# 0831.net
KiCad netlist of a schematic drawn in Altium Designer
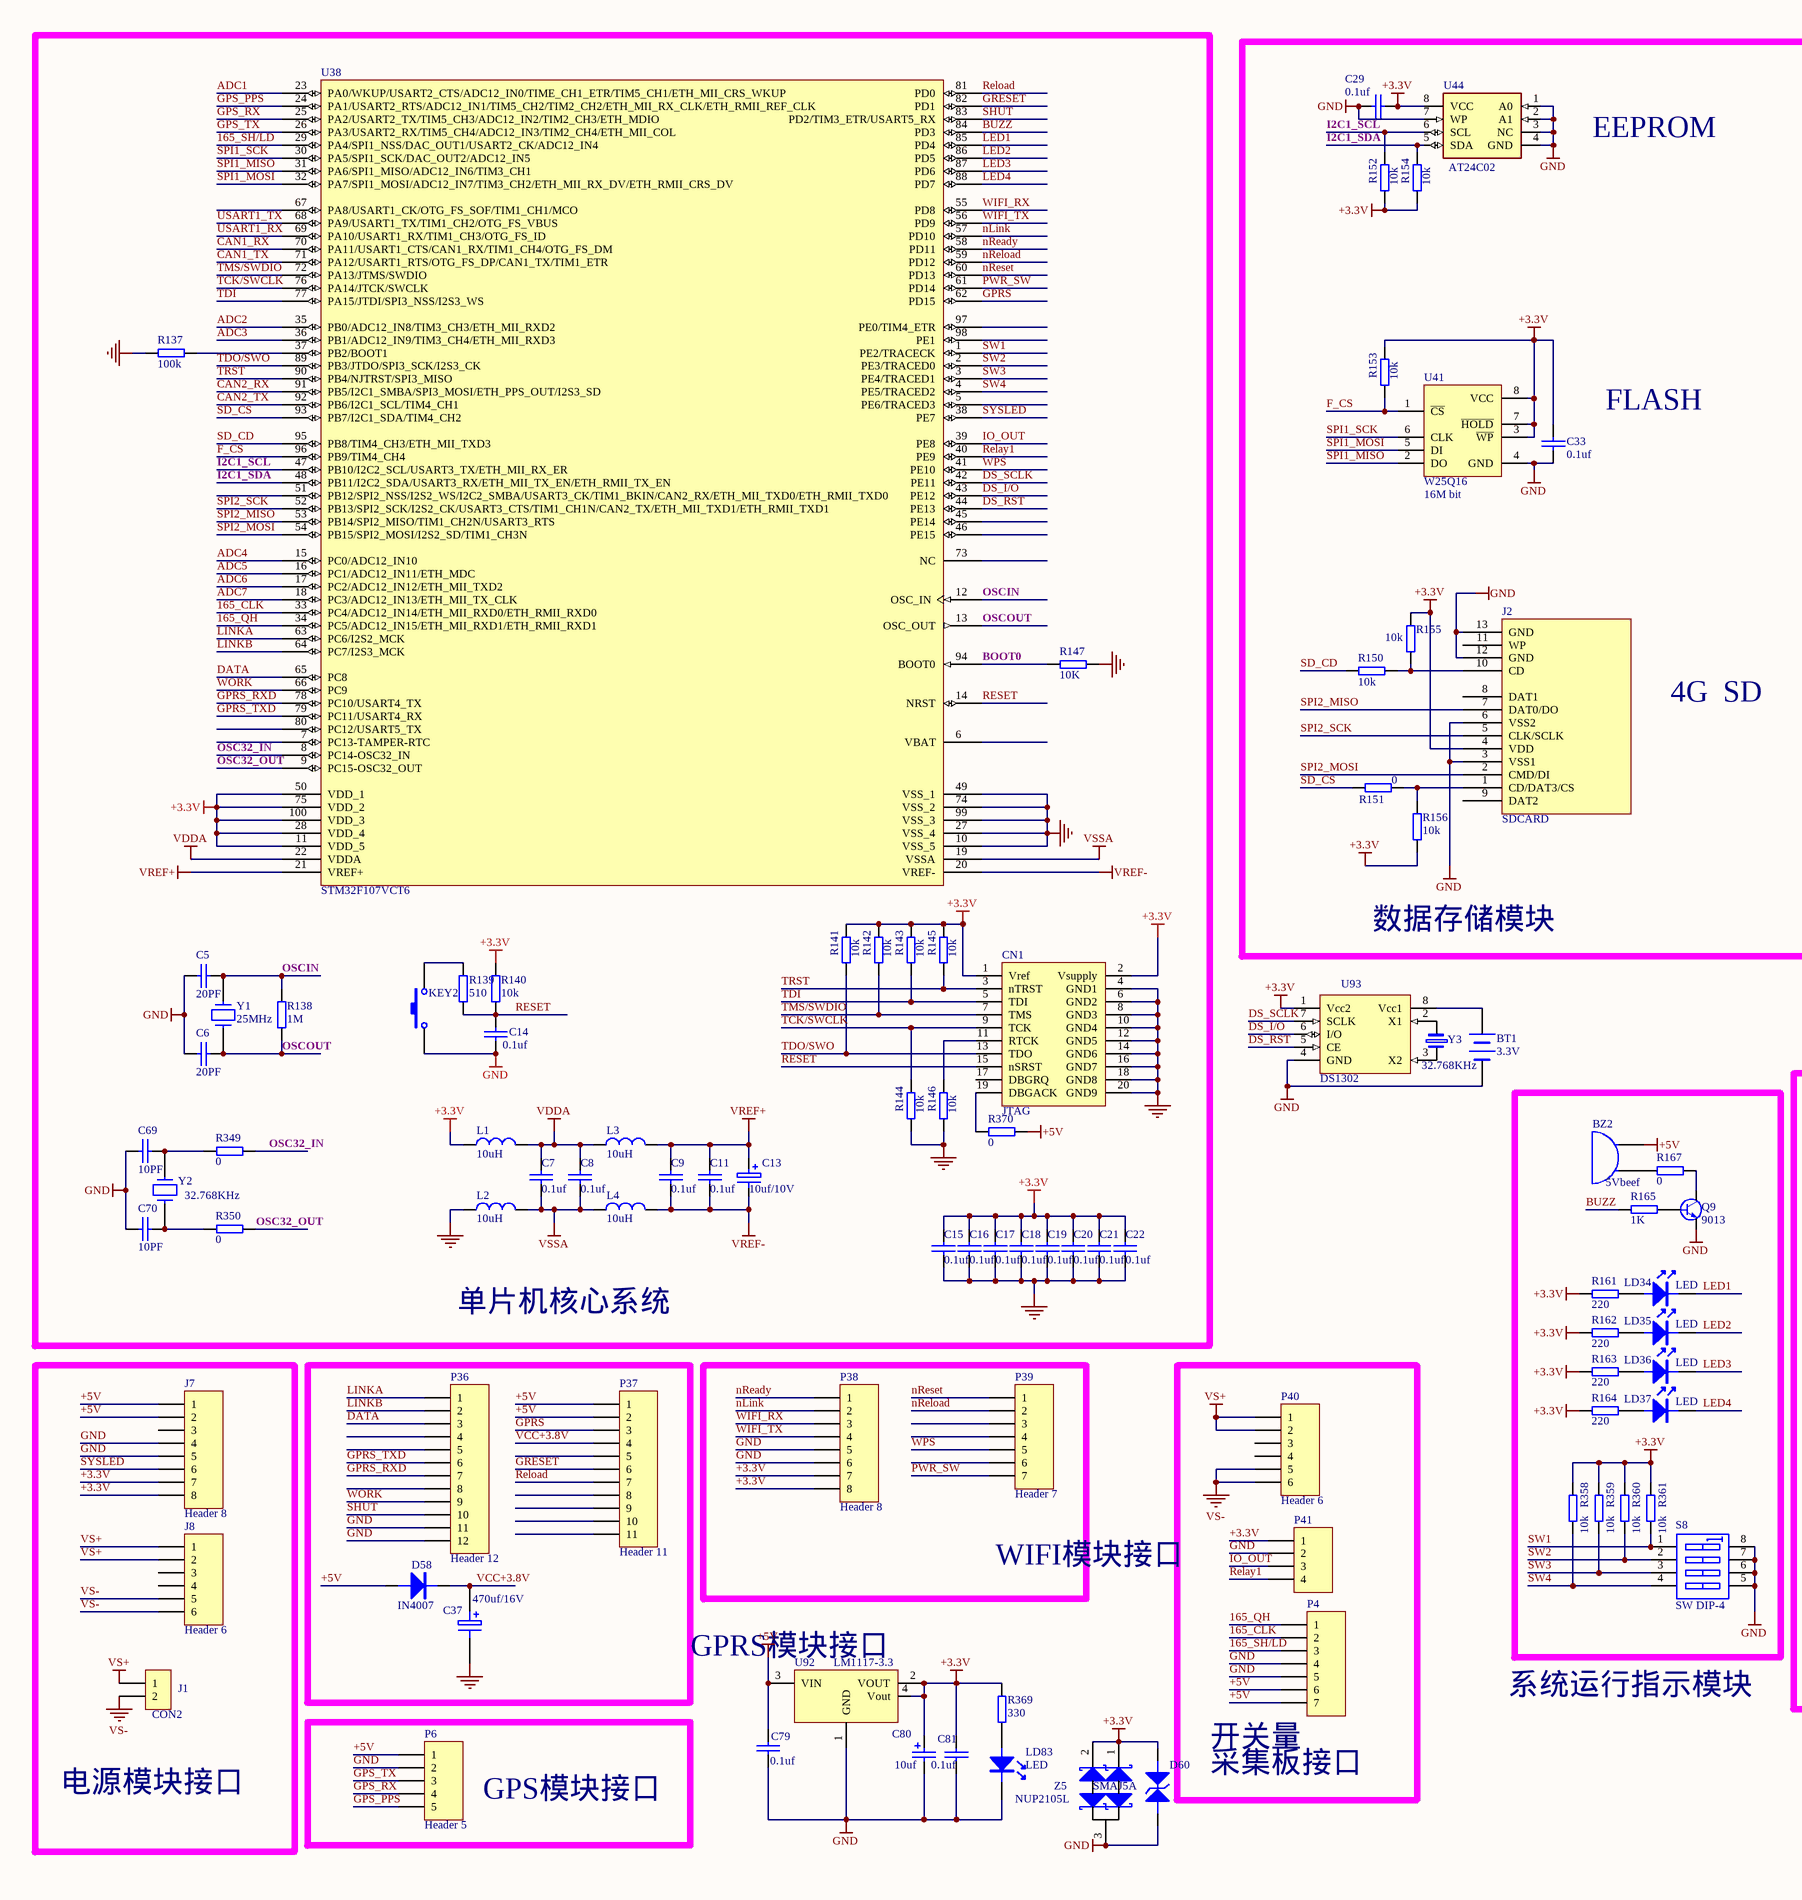
[diagram p0: 如意硬件系统模块0831.SchDoc, left]
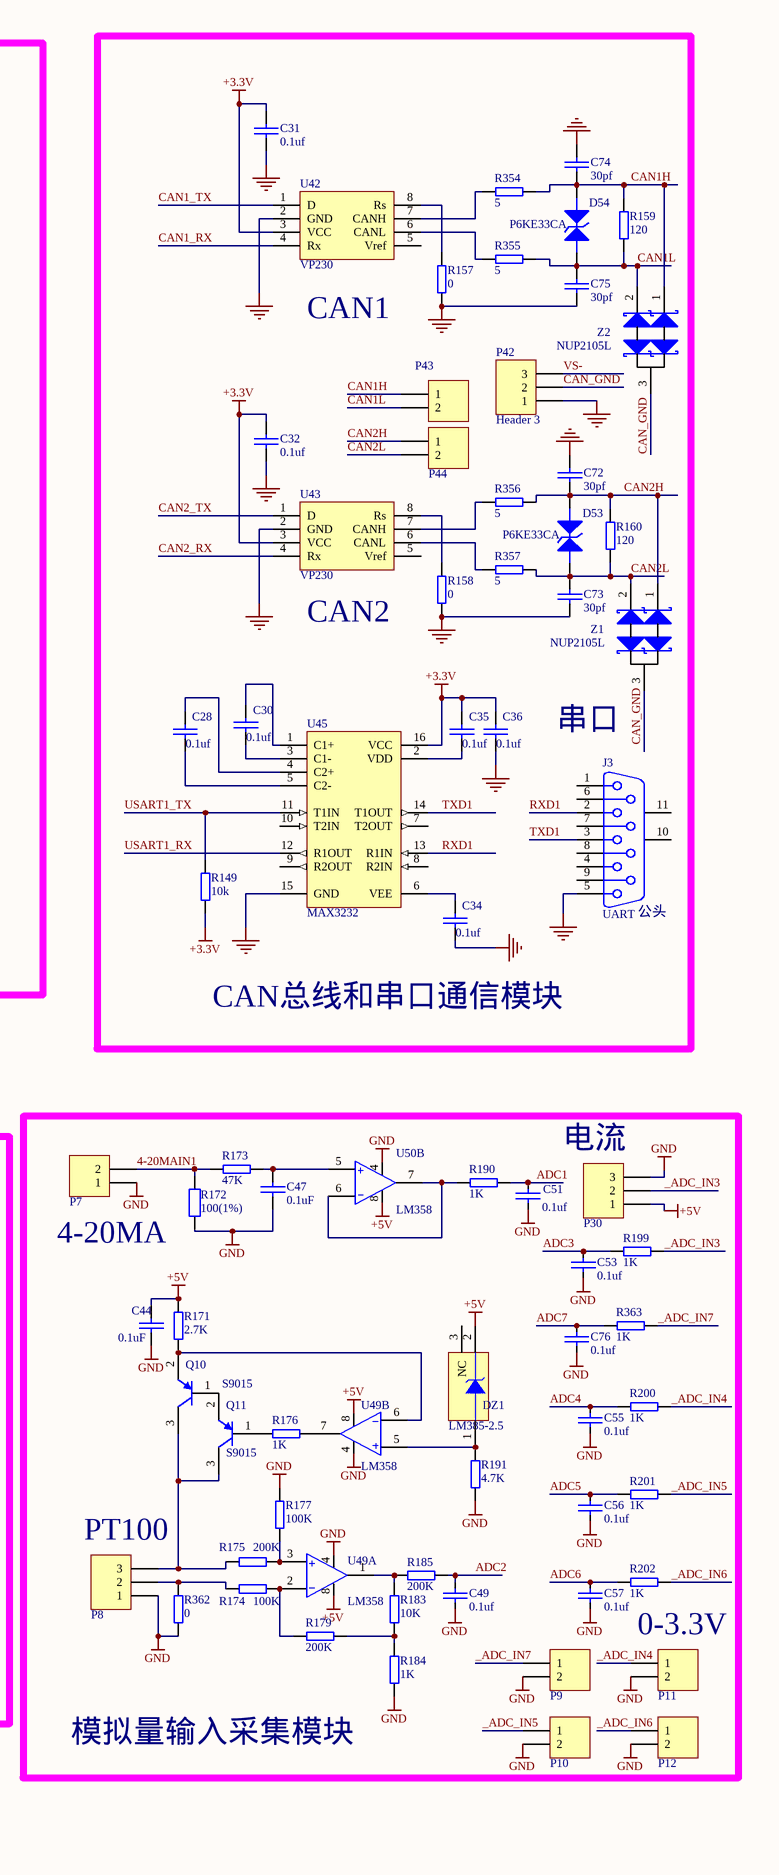
[diagram p1: 如意硬件系统模块0831.SchDoc, right]

(export (version "E")
  (design (tool "Eeschema 10.0.6"))
  (components
    (comp (ref "BT1")
      (value "3.3V")
      (footprint "BT2")
      (description "Battery")
      (libsource (lib "*") (part "BATTERY"))
    )
    (comp (ref "BZ2") (value "5Vbeef") (footprint "BEEP") (libsource (lib "*") (part "BUZZER")))
    (comp (ref "C5")
      (value "20PF")
      (footprint "0603C-1")
      (description "Capacitor")
      (libsource (lib "") (part "CAP_1"))
    )
    (comp (ref "C6")
      (value "20PF")
      (footprint "0603C-1")
      (description "Capacitor")
      (libsource (lib "") (part "CAP_1"))
    )
    (comp (ref "C7")
      (value "0.1uf")
      (footprint "0603C-1")
      (description "Capacitor")
      (libsource (lib "*") (part "CAP"))
    )
    (comp (ref "C8")
      (value "0.1uf")
      (footprint "0603C-1")
      (description "Capacitor")
      (libsource (lib "*") (part "CAP"))
    )
    (comp (ref "C9")
      (value "0.1uf")
      (footprint "0603C-1")
      (description "Capacitor")
      (libsource (lib "*") (part "CAP"))
    )
    (comp (ref "C11")
      (value "0.1uf")
      (footprint "0603C-1")
      (description "Capacitor")
      (libsource (lib "*") (part "CAP"))
    )
    (comp (ref "C13") (value "10uf/10V") (footprint "1206D-S") (libsource (lib "*") (part "JXC")))
    (comp (ref "C14")
      (value "0.1uf")
      (footprint "0603C-1")
      (description "Capacitor")
      (libsource (lib "") (part "CAP_1"))
    )
    (comp (ref "C15")
      (value "0.1uf")
      (footprint "0603C-1")
      (description "Capacitor")
      (libsource (lib "*") (part "CAP"))
    )
    (comp (ref "C16")
      (value "0.1uf")
      (footprint "0603C-1")
      (description "Capacitor")
      (libsource (lib "*") (part "CAP"))
    )
    (comp (ref "C17")
      (value "0.1uf")
      (footprint "0603C-1")
      (description "Capacitor")
      (libsource (lib "*") (part "CAP"))
    )
    (comp (ref "C18")
      (value "0.1uf")
      (footprint "0603C-1")
      (description "Capacitor")
      (libsource (lib "*") (part "CAP"))
    )
    (comp (ref "C19")
      (value "0.1uf")
      (footprint "0603C-1")
      (description "Capacitor")
      (libsource (lib "*") (part "CAP"))
    )
    (comp (ref "C20")
      (value "0.1uf")
      (footprint "0603C-1")
      (description "Capacitor")
      (libsource (lib "*") (part "CAP"))
    )
    (comp (ref "C21")
      (value "0.1uf")
      (footprint "0603C-1")
      (description "Capacitor")
      (libsource (lib "*") (part "CAP"))
    )
    (comp (ref "C22")
      (value "0.1uf")
      (footprint "0603C-1")
      (description "Capacitor")
      (libsource (lib "*") (part "CAP"))
    )
    (comp (ref "C28")
      (value "0.1uf")
      (footprint "0603C-1")
      (description "Capacitor")
      (libsource (lib "") (part "CAP_1"))
    )
    (comp (ref "C29")
      (value "0.1uf")
      (footprint "0603C-1")
      (description "Capacitor")
      (libsource (lib "") (part "CAP_1"))
    )
    (comp (ref "C30")
      (value "0.1uf")
      (footprint "0603C-1")
      (description "Capacitor")
      (libsource (lib "") (part "CAP_1"))
    )
    (comp (ref "C31")
      (value "0.1uf")
      (footprint "0603C-1")
      (description "Capacitor")
      (libsource (lib "") (part "CAP_1"))
    )
    (comp (ref "C32")
      (value "0.1uf")
      (footprint "0603C-1")
      (description "Capacitor")
      (libsource (lib "") (part "CAP_1"))
    )
    (comp (ref "C33")
      (value "0.1uf")
      (footprint "0603C-1")
      (description "Capacitor")
      (libsource (lib "") (part "CAP_1"))
    )
    (comp (ref "C34")
      (value "0.1uf")
      (footprint "0603C-1")
      (description "Capacitor")
      (libsource (lib "") (part "CAP_1"))
    )
    (comp (ref "C35")
      (value "0.1uf")
      (footprint "0603C-1")
      (description "Capacitor")
      (libsource (lib "") (part "CAP_1"))
    )
    (comp (ref "C36")
      (value "0.1uf")
      (footprint "0603C-1")
      (description "Capacitor")
      (libsource (lib "") (part "CAP_1"))
    )
    (comp (ref "C37")
      (value "470uf/16V")
      (footprint "C-RB-10")
      (description "Electrolytic Capacitor")
      (libsource (lib "*") (part "ELECTRO1"))
    )
    (comp (ref "C44")
      (value "0.1uF")
      (footprint "0603C-1")
      (description "Capacitor")
      (libsource (lib "") (part "CAP_1"))
    )
    (comp (ref "C47")
      (value "0.1uF")
      (footprint "0603C-1")
      (description "Capacitor")
      (libsource (lib "") (part "CAP_1"))
    )
    (comp (ref "C49") (value "0.1uf") (footprint "0805-1") (libsource (lib "*") (part "C")))
    (comp (ref "C51") (value "0.1uf") (footprint "0603C-1") (libsource (lib "*") (part "C")))
    (comp (ref "C53") (value "0.1uf") (footprint "0603C-1") (libsource (lib "*") (part "C")))
    (comp (ref "C55") (value "0.1uf") (footprint "0603C-1") (libsource (lib "*") (part "C")))
    (comp (ref "C56") (value "0.1uf") (footprint "0603C-1") (libsource (lib "*") (part "C")))
    (comp (ref "C57") (value "0.1uf") (footprint "0603C-1") (libsource (lib "*") (part "C")))
    (comp (ref "C69")
      (value "10PF")
      (footprint "0603C-1")
      (description "Capacitor")
      (libsource (lib "") (part "CAP_1"))
    )
    (comp (ref "C70")
      (value "10PF")
      (footprint "0603C-1")
      (description "Capacitor")
      (libsource (lib "") (part "CAP_1"))
    )
    (comp (ref "C72")
      (value "30pf")
      (footprint "0805-1")
      (description "Capacitor")
      (libsource (lib "") (part "CAP_1"))
    )
    (comp (ref "C73")
      (value "30pf")
      (footprint "0805-1")
      (description "Capacitor")
      (libsource (lib "") (part "CAP_1"))
    )
    (comp (ref "C74")
      (value "30pf")
      (footprint "0805-1")
      (description "Capacitor")
      (libsource (lib "") (part "CAP_1"))
    )
    (comp (ref "C75")
      (value "30pf")
      (footprint "0805-1")
      (description "Capacitor")
      (libsource (lib "") (part "CAP_1"))
    )
    (comp (ref "C76") (value "0.1uf") (footprint "0603C-1") (libsource (lib "*") (part "C")))
    (comp (ref "C79")
      (value "0.1uf")
      (footprint "0603C-1")
      (description "CAP")
      (libsource (lib "*") (part "CAP0"))
    )
    (comp (ref "C80") (value "10uf") (footprint "1206D-S") (libsource (lib "*") (part "ECAP")))
    (comp (ref "C81")
      (value "0.1uf")
      (footprint "0603C-1")
      (description "CAP")
      (libsource (lib "*") (part "CAP0"))
    )
    (comp (ref "CN1") (value "JTAG") (footprint "JTAG20 - 15") (libsource (lib "zongruyi") (part "JTAG20")))
    (comp (ref "D53") (value "P6KE33CA") (footprint "SMB") (libsource (lib "*") (part "TVS")))
    (comp (ref "D54") (value "P6KE33CA") (footprint "SMB") (libsource (lib "*") (part "TVS")))
    (comp (ref "D58")
      (value "IN4007")
      (footprint "SMB")
      (description "Diode")
      (libsource (lib "*") (part "DIODE"))
    )
    (comp (ref "D60") (value "SMAJ5A") (footprint "SMB") (libsource (lib "*") (part "TVS")))
    (comp (ref "DZ1")
      (value "LM385-2.5")
      (footprint "TO-92A")
      (description "Micropower Voltage Reference Diode")
      (fields (field (name "PUBLISHER") "Altium Limited"))
      (libsource (lib "*") (part "LM385BYZ-2.5"))
    )
    (comp (ref "J1")
      (value "CON2")
      (footprint "JXZ-2")
      (description "Connector")
      (libsource (lib "*") (part "CON2"))
    )
    (comp (ref "J2")
      (value "SDCARD")
      (footprint "SDC009-01-R2")
      (description "SD卡自弹")
      (libsource (lib "Fszhang") (part "SDCARD"))
    )
    (comp (ref "J3")
      (value "UART")
      (footprint "DB9-M")
      (description "Receptacle Assembly, 9 Position, Right Angle")
      (fields (field (name "PUBLISHER") "Altium Limited"))
      (libsource (lib "zongruyi") (part "D Connector 9"))
    )
    (comp (ref "J7")
      (value "Header 8")
      (footprint "HDR1X8")
      (description "Header, 8-Pin")
      (fields (field (name "PUBLISHER") "Altium Limited"))
      (libsource (lib "Miscellaneous Connectors") (part "Header 8"))
    )
    (comp (ref "J8")
      (value "Header 6")
      (footprint "HDR1X6")
      (description "接插件")
      (fields (field (name "PUBLISHER") "Altium Limited"))
      (libsource (lib "Miscellaneous Connectors") (part "Header 6"))
    )
    (comp (ref "KEY2")
      (value "SW-PB")
      (footprint "SW_PB4_A1")
      (description "Switch")
      (fields (field (name "PUBLISHER") "Altium Limited"))
      (libsource (lib "*") (part "SW-PB"))
    )
    (comp (ref "L1")
      (value "10uH")
      (footprint "1206")
      (description "电感")
      (fields (field (name "Comment") "Inductor") (field (name "PUBLISHER") "Altium Limited"))
      (libsource (lib "Fszhang") (part "Inductor"))
    )
    (comp (ref "L2")
      (value "10uH")
      (footprint "1206")
      (description "电感")
      (fields (field (name "Comment") "Inductor") (field (name "PUBLISHER") "Altium Limited"))
      (libsource (lib "Fszhang") (part "Inductor"))
    )
    (comp (ref "L3")
      (value "10uH")
      (footprint "1206")
      (description "电感")
      (fields (field (name "Comment") "Inductor") (field (name "PUBLISHER") "Altium Limited"))
      (libsource (lib "Fszhang") (part "Inductor"))
    )
    (comp (ref "L4")
      (value "10uH")
      (footprint "1206")
      (description "电感")
      (fields (field (name "Comment") "Inductor") (field (name "PUBLISHER") "Altium Limited"))
      (libsource (lib "Fszhang") (part "Inductor"))
    )
    (comp (ref "LD34") (value "LED") (footprint "LED_0805") (libsource (lib "*") (part "LED")))
    (comp (ref "LD35") (value "LED") (footprint "LED_0805") (libsource (lib "*") (part "LED")))
    (comp (ref "LD36") (value "LED") (footprint "LED_0805") (libsource (lib "*") (part "LED")))
    (comp (ref "LD37") (value "LED") (footprint "LED_0805") (libsource (lib "*") (part "LED")))
    (comp (ref "LD83") (value "LED") (footprint "LED_0805") (libsource (lib "") (part "LED_1")))
    (comp (ref "P4")
      (value "Header 7")
      (footprint "HDR1X7")
      (description "Header, 7-Pin")
      (fields (field (name "PUBLISHER") "Altium Limited"))
      (libsource (lib "Miscellaneous Connectors") (part "Header 7"))
    )
    (comp (ref "P6")
      (value "Header 5")
      (footprint "HDR1X5")
      (description "Header, 5-Pin")
      (fields (field (name "PUBLISHER") "Altium Limited"))
      (libsource (lib "Miscellaneous Connectors") (part "Header 5"))
    )
    (comp (ref "P7")
      (value "Header 2")
      (footprint "KF3.81-2P")
      (description "接插件")
      (fields (field (name "PUBLISHER") "Altium Limited"))
      (libsource (lib "") (part "Header 2_1"))
    )
    (comp (ref "P8")
      (value "Header 3")
      (footprint "KF3.81-3P")
      (description "接插件")
      (fields (field (name "PUBLISHER") "Altium Limited"))
      (libsource (lib "Fszhang") (part "Header 3"))
    )
    (comp (ref "P9")
      (value "Header 2")
      (footprint "KF3.81-2P")
      (description "接插件")
      (fields (field (name "PUBLISHER") "Altium Limited"))
      (libsource (lib "Fszhang") (part "Header 2"))
    )
    (comp (ref "P10")
      (value "Header 2")
      (footprint "KF3.81-2P")
      (description "接插件")
      (fields (field (name "PUBLISHER") "Altium Limited"))
      (libsource (lib "Fszhang") (part "Header 2"))
    )
    (comp (ref "P11")
      (value "Header 2")
      (footprint "KF3.81-2P")
      (description "接插件")
      (fields (field (name "PUBLISHER") "Altium Limited"))
      (libsource (lib "Fszhang") (part "Header 2"))
    )
    (comp (ref "P12")
      (value "Header 2")
      (footprint "KF3.81-2P")
      (description "接插件")
      (fields (field (name "PUBLISHER") "Altium Limited"))
      (libsource (lib "Fszhang") (part "Header 2"))
    )
    (comp (ref "P30")
      (value "Header 3")
      (footprint "KF3.81-3P")
      (description "接插件")
      (fields (field (name "PUBLISHER") "Altium Limited"))
      (libsource (lib "Fszhang") (part "Header 3"))
    )
    (comp (ref "P36")
      (value "Header 12")
      (footprint "HDR1X12")
      (description "Header, 12-Pin")
      (fields (field (name "PUBLISHER") "Altium Limited"))
      (libsource (lib "Miscellaneous Connectors") (part "Header 12"))
    )
    (comp (ref "P37")
      (value "Header 11")
      (footprint "HDR1X11")
      (description "Header, 11-Pin")
      (fields (field (name "PUBLISHER") "Altium Limited"))
      (libsource (lib "Miscellaneous Connectors") (part "Header 11"))
    )
    (comp (ref "P38")
      (value "Header 8")
      (footprint "HDR1X8")
      (description "Header, 8-Pin")
      (fields (field (name "PUBLISHER") "Altium Limited"))
      (libsource (lib "Miscellaneous Connectors") (part "Header 8"))
    )
    (comp (ref "P39")
      (value "Header 7")
      (footprint "HDR1X7")
      (description "Header, 7-Pin")
      (fields (field (name "PUBLISHER") "Altium Limited"))
      (libsource (lib "Miscellaneous Connectors") (part "Header 7"))
    )
    (comp (ref "P40")
      (value "Header 6")
      (footprint "HDR1X6")
      (description "Header, 6-Pin")
      (fields (field (name "PUBLISHER") "Altium Limited"))
      (libsource (lib "Miscellaneous Connectors") (part "Header 6"))
    )
    (comp (ref "P41")
      (value "Header 4")
      (footprint "HDR1X4")
      (description "Header, 4-Pin")
      (fields (field (name "PUBLISHER") "Altium Limited"))
      (libsource (lib "Miscellaneous Connectors") (part "Header 4"))
    )
    (comp (ref "P42")
      (value "Header 3")
      (footprint "HDR1X3")
      (description "Header, 3-Pin")
      (fields (field (name "PUBLISHER") "Altium Limited"))
      (libsource (lib "Miscellaneous Connectors") (part "Header 3"))
    )
    (comp (ref "P43")
      (value "Header 2")
      (footprint "KF3.81-2P")
      (description "接插件")
      (fields (field (name "PUBLISHER") "Altium Limited"))
      (libsource (lib "Fszhang") (part "Header 2"))
    )
    (comp (ref "P44")
      (value "Header 2")
      (footprint "KF3.81-2P")
      (description "接插件")
      (fields (field (name "PUBLISHER") "Altium Limited"))
      (libsource (lib "Fszhang") (part "Header 2"))
    )
    (comp (ref "Q9") (value "9013") (footprint "SOT23-BCE") (libsource (lib "*") (part "NPN")))
    (comp (ref "Q10")
      (value "S9015")
      (footprint "SOT-23")
      (description "PNP三极管")
      (fields (field (name "PUBLISHER") "Altium Limited"))
      (libsource (lib "zongruyi") (part "S9015_1"))
    )
    (comp (ref "Q11")
      (value "S9015")
      (footprint "SOT-23")
      (description "PNP三极管")
      (fields (field (name "PUBLISHER") "Altium Limited"))
      (libsource (lib "zongruyi") (part "S9015_1"))
    )
    (comp (ref "R137") (value "100k") (footprint "0603R-1") (libsource (lib "*") (part "RES2")))
    (comp (ref "R138") (value "1M") (footprint "0603R-1") (libsource (lib "*") (part "RES-2")))
    (comp (ref "R139") (value "510") (footprint "0603R-1") (libsource (lib "*") (part "RES-2")))
    (comp (ref "R140") (value "10k") (footprint "0603R-1") (libsource (lib "*") (part "RES2")))
    (comp (ref "R141") (value "10k") (footprint "0603R-1") (libsource (lib "*") (part "RES2")))
    (comp (ref "R142") (value "10k") (footprint "0603R-1") (libsource (lib "*") (part "RES2")))
    (comp (ref "R143") (value "10k") (footprint "0603R-1") (libsource (lib "*") (part "RES2")))
    (comp (ref "R144") (value "10k") (footprint "0603R-1") (libsource (lib "*") (part "RES2")))
    (comp (ref "R145") (value "10k") (footprint "0603R-1") (libsource (lib "*") (part "RES2")))
    (comp (ref "R146") (value "10k") (footprint "0603R-1") (libsource (lib "*") (part "RES2")))
    (comp (ref "R147") (value "10K") (footprint "0603R-1") (libsource (lib "*") (part "RES-2")))
    (comp (ref "R149") (value "10k") (footprint "0603R-1") (libsource (lib "*") (part "RES2")))
    (comp (ref "R150") (value "10k") (footprint "0603R-1") (libsource (lib "*") (part "RES2")))
    (comp (ref "R151") (value "0") (footprint "0603R-1") (libsource (lib "*") (part "RES2")))
    (comp (ref "R152") (value "10k") (footprint "0603R-1") (libsource (lib "*") (part "RES2")))
    (comp (ref "R153") (value "10k") (footprint "0603R-1") (libsource (lib "*") (part "RES2")))
    (comp (ref "R154") (value "10k") (footprint "0603R-1") (libsource (lib "*") (part "RES2")))
    (comp (ref "R155") (value "10k") (footprint "0603R-1") (libsource (lib "*") (part "RES2")))
    (comp (ref "R156") (value "10k") (footprint "0603R-1") (libsource (lib "*") (part "RES2")))
    (comp (ref "R157") (value "0") (footprint "0603R-1") (libsource (lib "*") (part "RES2")))
    (comp (ref "R158") (value "0") (footprint "0603R-1") (libsource (lib "*") (part "RES2")))
    (comp (ref "R159") (value "120") (footprint "0805-1") (libsource (lib "*") (part "RES2")))
    (comp (ref "R160") (value "120") (footprint "0805-1") (libsource (lib "*") (part "RES2")))
    (comp (ref "R161") (value "220") (footprint "0603R-1") (libsource (lib "") (part "RES-2_1")))
    (comp (ref "R162") (value "220") (footprint "0603R-1") (libsource (lib "") (part "RES-2_1")))
    (comp (ref "R163") (value "220") (footprint "0603R-1") (libsource (lib "") (part "RES-2_1")))
    (comp (ref "R164") (value "220") (footprint "0603R-1") (libsource (lib "") (part "RES-2_1")))
    (comp (ref "R165") (value "1K") (footprint "0603R-1") (libsource (lib "") (part "RES-2_1")))
    (comp (ref "R167") (value "0") (footprint "0603R-1") (libsource (lib "") (part "RES-2_1")))
    (comp (ref "R171") (value "2.7K") (footprint "AXIAL0.4") (libsource (lib "") (part "RES-2_1")))
    (comp (ref "R172")
      (value "100(1%)")
      (footprint "AXIAL0.4")
      (description "Resistor")
      (fields (field (name "PUBLISHER") "Altium Limited"))
      (libsource (lib "*") (part "Res2"))
    )
    (comp (ref "R173") (value "47K") (footprint "0603R-1") (libsource (lib "*") (part "RES-2")))
    (comp (ref "R174") (value "100K") (footprint "0805-1") (libsource (lib "") (part "RES-2_1")))
    (comp (ref "R175") (value "200K") (footprint "0805-1") (libsource (lib "") (part "RES-2_1")))
    (comp (ref "R176") (value "1K") (footprint "0603R-1") (libsource (lib "") (part "RES-2_1")))
    (comp (ref "R177") (value "100K") (footprint "0805-1") (libsource (lib "") (part "RES-2_1")))
    (comp (ref "R179") (value "200K") (footprint "0805-1") (libsource (lib "") (part "RES-2_1")))
    (comp (ref "R183") (value "10K") (footprint "0805-1") (libsource (lib "") (part "RES-2_1")))
    (comp (ref "R184") (value "1K") (footprint "0805-1") (libsource (lib "") (part "RES-2_1")))
    (comp (ref "R185") (value "200K") (footprint "0805-1") (libsource (lib "") (part "RES-2_1")))
    (comp (ref "R190") (value "1K") (footprint "0603R-1") (libsource (lib "*") (part "RES-2")))
    (comp (ref "R191") (value "4.7K") (footprint "0603R-1") (libsource (lib "") (part "RES-2_1")))
    (comp (ref "R199") (value "1K") (footprint "0603R-1") (libsource (lib "*") (part "RES-2")))
    (comp (ref "R200") (value "1K") (footprint "0603R-1") (libsource (lib "*") (part "RES-2")))
    (comp (ref "R201") (value "1K") (footprint "0603R-1") (libsource (lib "*") (part "RES-2")))
    (comp (ref "R202") (value "1K") (footprint "0603R-1") (libsource (lib "*") (part "RES-2")))
    (comp (ref "R349") (value "0") (footprint "0603R-1") (libsource (lib "*") (part "RES-2")))
    (comp (ref "R350") (value "0") (footprint "0603R-1") (libsource (lib "*") (part "RES-2")))
    (comp (ref "R354") (value "5") (footprint "0805-1") (libsource (lib "*") (part "RES2")))
    (comp (ref "R355") (value "5") (footprint "0805-1") (libsource (lib "*") (part "RES2")))
    (comp (ref "R356") (value "5") (footprint "0805-1") (libsource (lib "*") (part "RES2")))
    (comp (ref "R357") (value "5") (footprint "0805-1") (libsource (lib "*") (part "RES2")))
    (comp (ref "R358") (value "10k") (footprint "0603R-1") (libsource (lib "*") (part "RES2")))
    (comp (ref "R359") (value "10k") (footprint "0603R-1") (libsource (lib "*") (part "RES2")))
    (comp (ref "R360") (value "10k") (footprint "0603R-1") (libsource (lib "*") (part "RES2")))
    (comp (ref "R361") (value "10k") (footprint "0603R-1") (libsource (lib "*") (part "RES2")))
    (comp (ref "R362") (value "0") (footprint "0603R-1") (libsource (lib "*") (part "RES2")))
    (comp (ref "R363") (value "1K") (footprint "0603R-1") (libsource (lib "*") (part "RES-2")))
    (comp (ref "R369") (value "330") (footprint "0603R-1") (libsource (lib "*") (part "RES-2")))
    (comp (ref "R370") (value "0") (footprint "0603R-1") (libsource (lib "*") (part "RES2")))
    (comp (ref "S8")
      (value "SW DIP-4")
      (footprint "DIP-8")
      (description "编码开关")
      (fields (field (name "PUBLISHER") "Altium Limited"))
      (libsource (lib "Fszhang") (part "SW DIP-4"))
    )
    (comp (ref "U38")
      (value "STM32F107VCT6")
      (footprint "LQFP100_M")
      (libsource (lib "金龙107原理图封装库") (part "STM32F107VCT6"))
    )
    (comp (ref "U41")
      (value "W25Q16")
      (footprint "SOIC8_W")
      (description "SPI FLASH")
      (fields (field (name "MEMORY") "16M bit"))
      (libsource (lib "Fszhang") (part "W25QXX"))
    )
    (comp (ref "U42")
      (value "VP230")
      (footprint "NSO8_N")
      (description "CAN芯片")
      (libsource (lib "Fszhang") (part "SN65HVD230"))
    )
    (comp (ref "U43")
      (value "VP230")
      (footprint "NSO8_N")
      (description "CAN芯片")
      (libsource (lib "Fszhang") (part "SN65HVD230"))
    )
    (comp (ref "U44") (value "AT24C02") (footprint "SO-8") (libsource (lib "*") (part "AT24C128")))
    (comp (ref "U45")
      (value "MAX3232")
      (footprint "NSO16_M")
      (description "+5V Powered, Multi-Channel RS-232 Driver/Receiver")
      (fields (field (name "PUBLISHER") "Altium Limited"))
      (libsource (lib "Fszhang") (part "MAX232"))
    )
    (comp (ref "U49") (value "LM358") (footprint "SO-8") (libsource (lib "*") (part "LM358")))
    (comp (ref "U50") (value "LM358") (footprint "SO-8") (libsource (lib "*") (part "LM358")))
    (comp (ref "U92") (value "LM1117-3.3") (footprint "ASM1117") (libsource (lib "*") (part "LM1117")))
    (comp (ref "U93") (value "DS1302") (footprint "SO-8") (libsource (lib "*") (part "DS1302")))
    (comp (ref "Y1")
      (value "25MHz")
      (footprint "XTAL1")
      (description "Crystal")
      (libsource (lib "*") (part "CRYSTAL"))
    )
    (comp (ref "Y2")
      (value "32.768KHz")
      (footprint "XTAL4")
      (description "Crystal")
      (libsource (lib "*") (part "CRYSTAL"))
    )
    (comp (ref "Y3") (value "32.768KHz") (footprint "XTAL5") (libsource (lib "*") (part "XTAL")))
    (comp (ref "Z1")
      (value "NUP2105L")
      (footprint "SOT-23")
      (description "过压保护")
      (libsource (lib "Fszhang") (part "PESD1CAN"))
    )
    (comp (ref "Z2")
      (value "NUP2105L")
      (footprint "SOT-23")
      (description "过压保护")
      (libsource (lib "Fszhang") (part "PESD1CAN"))
    )
    (comp (ref "Z5")
      (value "NUP2105L")
      (footprint "SOT-23")
      (description "过压保护")
      (libsource (lib "Fszhang") (part "PESD1CAN"))
    )
  )
  (nets
    (net (code "1") (name "+3.3V") (class "Default")
      (node (ref "C15") (pin "2") (pinfunction "2_2") (pintype "passive"))
      (node (ref "C16") (pin "2") (pinfunction "2_2") (pintype "passive"))
      (node (ref "C17") (pin "2") (pinfunction "2_2") (pintype "passive"))
      (node (ref "C18") (pin "2") (pinfunction "2_2") (pintype "passive"))
      (node (ref "C19") (pin "2") (pinfunction "2_2") (pintype "passive"))
      (node (ref "C20") (pin "2") (pinfunction "2_2") (pintype "passive"))
      (node (ref "C21") (pin "2") (pinfunction "2_2") (pintype "passive"))
      (node (ref "C22") (pin "2") (pinfunction "2_2") (pintype "passive"))
      (node (ref "C29") (pin "2") (pinfunction "2_2") (pintype "passive"))
      (node (ref "C31") (pin "2") (pinfunction "2_2") (pintype "passive"))
      (node (ref "C32") (pin "2") (pinfunction "2_2") (pintype "passive"))
      (node (ref "C33") (pin "2") (pinfunction "2_2") (pintype "passive"))
      (node (ref "C35") (pin "2") (pinfunction "2_2") (pintype "passive"))
      (node (ref "C36") (pin "2") (pinfunction "2_2") (pintype "passive"))
      (node (ref "C80") (pin "1") (pintype "passive"))
      (node (ref "C81") (pin "2") (pintype "passive"))
      (node (ref "CN1") (pin "1") (pinfunction "Vref_1") (pintype "passive"))
      (node (ref "CN1") (pin "2") (pinfunction "Vsupply_2") (pintype "passive"))
      (node (ref "D60") (pin "2") (pinfunction "K_2") (pintype "passive"))
      (node (ref "J2") (pin "4") (pinfunction "VDD_4") (pintype "passive"))
      (node (ref "J7") (pin "7") (pinfunction "7_7") (pintype "passive"))
      (node (ref "J7") (pin "8") (pinfunction "8_8") (pintype "passive"))
      (node (ref "L1") (pin "1") (pinfunction "1_1") (pintype "passive"))
      (node (ref "P38") (pin "7") (pinfunction "7_7") (pintype "passive"))
      (node (ref "P38") (pin "8") (pinfunction "8_8") (pintype "passive"))
      (node (ref "P41") (pin "1") (pinfunction "1_1") (pintype "passive"))
      (node (ref "R140") (pin "2") (pinfunction "2_2") (pintype "passive"))
      (node (ref "R141") (pin "2") (pinfunction "2_2") (pintype "passive"))
      (node (ref "R142") (pin "2") (pinfunction "2_2") (pintype "passive"))
      (node (ref "R143") (pin "2") (pinfunction "2_2") (pintype "passive"))
      (node (ref "R145") (pin "2") (pinfunction "2_2") (pintype "passive"))
      (node (ref "R149") (pin "2") (pinfunction "2_2") (pintype "passive"))
      (node (ref "R152") (pin "1") (pinfunction "1_1") (pintype "passive"))
      (node (ref "R153") (pin "2") (pinfunction "2_2") (pintype "passive"))
      (node (ref "R154") (pin "1") (pinfunction "1_1") (pintype "passive"))
      (node (ref "R155") (pin "1") (pinfunction "1_1") (pintype "passive"))
      (node (ref "R156") (pin "2") (pinfunction "2_2") (pintype "passive"))
      (node (ref "R161") (pin "1") (pinfunction "1_1") (pintype "passive"))
      (node (ref "R162") (pin "1") (pinfunction "1_1") (pintype "passive"))
      (node (ref "R163") (pin "1") (pinfunction "1_1") (pintype "passive"))
      (node (ref "R164") (pin "1") (pinfunction "1_1") (pintype "passive"))
      (node (ref "R358") (pin "2") (pinfunction "2_2") (pintype "passive"))
      (node (ref "R359") (pin "2") (pinfunction "2_2") (pintype "passive"))
      (node (ref "R360") (pin "2") (pinfunction "2_2") (pintype "passive"))
      (node (ref "R361") (pin "2") (pinfunction "2_2") (pintype "passive"))
      (node (ref "R369") (pin "1") (pinfunction "1_1") (pintype "passive"))
      (node (ref "U38") (pin "100") (pinfunction "VDD_3_100") (pintype "passive"))
      (node (ref "U38") (pin "11") (pinfunction "VDD_5_11") (pintype "passive"))
      (node (ref "U38") (pin "28") (pinfunction "VDD_4_28") (pintype "passive"))
      (node (ref "U38") (pin "50") (pinfunction "VDD_1_50") (pintype "passive"))
      (node (ref "U38") (pin "75") (pinfunction "VDD_2_75") (pintype "passive"))
      (node (ref "U41") (pin "3") (pinfunction "~{WP}_3") (pintype "passive"))
      (node (ref "U41") (pin "7") (pinfunction "~{HOLD}_7") (pintype "passive"))
      (node (ref "U41") (pin "8") (pinfunction "VCC_8") (pintype "passive"))
      (node (ref "U42") (pin "3") (pinfunction "VCC_3") (pintype "passive"))
      (node (ref "U43") (pin "3") (pinfunction "VCC_3") (pintype "passive"))
      (node (ref "U44") (pin "8") (pinfunction "VCC_8") (pintype "power_in"))
      (node (ref "U45") (pin "16") (pinfunction "VCC_16") (pintype "power_in"))
      (node (ref "U92") (pin "2") (pinfunction "VOUT_2") (pintype "passive"))
      (node (ref "U92") (pin "4") (pinfunction "Vout_4") (pintype "passive"))
      (node (ref "U93") (pin "1") (pinfunction "Vcc2_1") (pintype "power_in"))
      (node (ref "Z5") (pin "1") (pintype "passive"))
      (node (ref "Z5") (pin "2") (pintype "passive"))
    )
    (net (code "2") (name "+5V") (class "Default")
      (node (ref "BZ2") (pin "1") (pinfunction "A_1") (pintype "passive"))
      (node (ref "C44") (pin "2") (pinfunction "2_2") (pintype "passive"))
      (node (ref "C79") (pin "2") (pintype "passive"))
      (node (ref "D58") (pin "1") (pinfunction "A_1") (pintype "passive"))
      (node (ref "DZ1") (pin "2") (pinfunction "V+_2") (pintype "power_in"))
      (node (ref "J7") (pin "1") (pinfunction "1_1") (pintype "passive"))
      (node (ref "J7") (pin "2") (pinfunction "2_2") (pintype "passive"))
      (node (ref "P30") (pin "1") (pinfunction "1_1") (pintype "passive"))
      (node (ref "P37") (pin "1") (pinfunction "1_1") (pintype "passive"))
      (node (ref "P37") (pin "2") (pinfunction "2_2") (pintype "passive"))
      (node (ref "P4") (pin "6") (pinfunction "6_6") (pintype "passive"))
      (node (ref "P4") (pin "7") (pinfunction "7_7") (pintype "passive"))
      (node (ref "P6") (pin "1") (pinfunction "1_1") (pintype "passive"))
      (node (ref "R171") (pin "2") (pinfunction "2_2") (pintype "passive"))
      (node (ref "R370") (pin "1") (pinfunction "1_1") (pintype "passive"))
      (node (ref "U49") (pin "8") (pinfunction "VCC_8") (pintype "passive"))
      (node (ref "U50") (pin "8") (pinfunction "VCC_8") (pintype "passive"))
      (node (ref "U92") (pin "3") (pinfunction "VIN_3") (pintype "passive"))
    )
    (net (code "3") (name "/4-20MAIN1") (class "Default")
      (node (ref "P7") (pin "2") (pinfunction "2_2") (pintype "passive"))
      (node (ref "R172") (pin "2") (pinfunction "2_2") (pintype "passive"))
      (node (ref "R173") (pin "2") (pinfunction "2_2") (pintype "passive"))
    )
    (net (code "4") (name "/165_CLK") (class "Default")
      (node (ref "P4") (pin "2") (pinfunction "2_2") (pintype "passive"))
      (node (ref "U38") (pin "33") (pinfunction "PC4/ADC12_IN14/ETH_MII_RXD0/ETH_RMII_RXD0_33") (pintype "bidirectional"))
    )
    (net (code "5") (name "/165_QH") (class "Default")
      (node (ref "P4") (pin "1") (pinfunction "1_1") (pintype "passive"))
      (node (ref "U38") (pin "34") (pinfunction "PC5/ADC12_IN15/ETH_MII_RXD1/ETH_RMII_RXD1_34") (pintype "bidirectional"))
    )
    (net (code "6") (name "/165_SH{slash}LD") (class "Default")
      (node (ref "P4") (pin "3") (pinfunction "3_3") (pintype "passive"))
      (node (ref "U38") (pin "29") (pinfunction "PA4/SPI1_NSS/DAC_OUT1/USART2_CK/ADC12_IN4_29") (pintype "bidirectional"))
    )
    (net (code "7") (name "/ADC1") (class "Default")
      (node (ref "C51") (pin "1") (pinfunction "1_1") (pintype "passive"))
      (node (ref "R190") (pin "2") (pinfunction "2_2") (pintype "passive"))
      (node (ref "U38") (pin "23") (pinfunction "PA0/WKUP/USART2_CTS/ADC12_IN0/TIME_CH1_ETR/TIM5_CH1/ETH_MII_CRS_WKUP_23") (pintype "bidirectional"))
    )
    (net (code "8") (name "/ADC2") (class "Default")
      (node (ref "C49") (pin "1") (pinfunction "1_1") (pintype "passive"))
      (node (ref "R185") (pin "2") (pinfunction "2_2") (pintype "passive"))
      (node (ref "U38") (pin "35") (pinfunction "PB0/ADC12_IN8/TIM3_CH3/ETH_MII_RXD2_35") (pintype "bidirectional"))
    )
    (net (code "9") (name "/ADC3") (class "Default")
      (node (ref "C53") (pin "1") (pinfunction "1_1") (pintype "passive"))
      (node (ref "R199") (pin "1") (pinfunction "1_1") (pintype "passive"))
      (node (ref "U38") (pin "36") (pinfunction "PB1/ADC12_IN9/TIM3_CH4/ETH_MII_RXD3_36") (pintype "bidirectional"))
    )
    (net (code "10") (name "/ADC4") (class "Default")
      (node (ref "C55") (pin "1") (pinfunction "1_1") (pintype "passive"))
      (node (ref "R200") (pin "1") (pinfunction "1_1") (pintype "passive"))
      (node (ref "U38") (pin "15") (pinfunction "PC0/ADC12_IN10_15") (pintype "bidirectional"))
    )
    (net (code "11") (name "/ADC5") (class "Default")
      (node (ref "C56") (pin "1") (pinfunction "1_1") (pintype "passive"))
      (node (ref "R201") (pin "1") (pinfunction "1_1") (pintype "passive"))
      (node (ref "U38") (pin "16") (pinfunction "PC1/ADC12_IN11/ETH_MDC_16") (pintype "bidirectional"))
    )
    (net (code "12") (name "/ADC6") (class "Default")
      (node (ref "C57") (pin "1") (pinfunction "1_1") (pintype "passive"))
      (node (ref "R202") (pin "1") (pinfunction "1_1") (pintype "passive"))
      (node (ref "U38") (pin "17") (pinfunction "PC2/ADC12_IN12/ETH_MII_TXD2_17") (pintype "bidirectional"))
    )
    (net (code "13") (name "/ADC7") (class "Default")
      (node (ref "C76") (pin "1") (pinfunction "1_1") (pintype "passive"))
      (node (ref "R363") (pin "1") (pinfunction "1_1") (pintype "passive"))
      (node (ref "U38") (pin "18") (pinfunction "PC3/ADC12_IN13/ETH_MII_TX_CLK_18") (pintype "bidirectional"))
    )
    (net (code "14") (name "/BOOT0") (class "Default")
      (node (ref "R147") (pin "2") (pinfunction "2_2") (pintype "passive"))
      (node (ref "U38") (pin "94") (pinfunction "BOOT0_94") (pintype "input"))
    )
    (net (code "15") (name "/BUZZ") (class "Default")
      (node (ref "R165") (pin "2") (pinfunction "2_2") (pintype "passive"))
      (node (ref "U38") (pin "84") (pinfunction "PD3_84") (pintype "bidirectional"))
    )
    (net (code "16") (name "/CAN1H") (class "Default")
      (node (ref "C74") (pin "1") (pinfunction "1_1") (pintype "passive"))
      (node (ref "D54") (pin "2") (pinfunction "K_2") (pintype "passive"))
      (node (ref "P43") (pin "1") (pinfunction "1_1") (pintype "passive"))
      (node (ref "R159") (pin "1") (pinfunction "1_1") (pintype "passive"))
      (node (ref "R354") (pin "2") (pinfunction "2_2") (pintype "passive"))
      (node (ref "Z2") (pin "1") (pintype "passive"))
    )
    (net (code "17") (name "/CAN1L") (class "Default")
      (node (ref "C75") (pin "2") (pinfunction "2_2") (pintype "passive"))
      (node (ref "D54") (pin "1") (pinfunction "A_1") (pintype "passive"))
      (node (ref "P43") (pin "2") (pinfunction "2_2") (pintype "passive"))
      (node (ref "R159") (pin "2") (pinfunction "2_2") (pintype "passive"))
      (node (ref "R355") (pin "2") (pinfunction "2_2") (pintype "passive"))
      (node (ref "Z2") (pin "2") (pintype "passive"))
    )
    (net (code "18") (name "/CAN1_RX") (class "Default")
      (node (ref "U38") (pin "70") (pinfunction "PA11/USART1_CTS/CAN1_RX/TIM1_CH4/OTG_FS_DM_70") (pintype "bidirectional"))
      (node (ref "U42") (pin "4") (pinfunction "Rx_4") (pintype "passive"))
    )
    (net (code "19") (name "/CAN1_TX") (class "Default")
      (node (ref "U38") (pin "71") (pinfunction "PA12/USART1_RTS/OTG_FS_DP/CAN1_TX/TIM1_ETR_71") (pintype "bidirectional"))
      (node (ref "U42") (pin "1") (pinfunction "D_1") (pintype "passive"))
    )
    (net (code "20") (name "/CAN2H") (class "Default")
      (node (ref "C72") (pin "1") (pinfunction "1_1") (pintype "passive"))
      (node (ref "D53") (pin "2") (pinfunction "K_2") (pintype "passive"))
      (node (ref "P44") (pin "1") (pinfunction "1_1") (pintype "passive"))
      (node (ref "R160") (pin "1") (pinfunction "1_1") (pintype "passive"))
      (node (ref "R356") (pin "2") (pinfunction "2_2") (pintype "passive"))
      (node (ref "Z1") (pin "1") (pintype "passive"))
    )
    (net (code "21") (name "/CAN2L") (class "Default")
      (node (ref "C73") (pin "2") (pinfunction "2_2") (pintype "passive"))
      (node (ref "D53") (pin "1") (pinfunction "A_1") (pintype "passive"))
      (node (ref "P44") (pin "2") (pinfunction "2_2") (pintype "passive"))
      (node (ref "R160") (pin "2") (pinfunction "2_2") (pintype "passive"))
      (node (ref "R357") (pin "2") (pinfunction "2_2") (pintype "passive"))
      (node (ref "Z1") (pin "2") (pintype "passive"))
    )
    (net (code "22") (name "/CAN2_RX") (class "Default")
      (node (ref "U38") (pin "91") (pinfunction "PB5/I2C1_SMBA/SPI3_MOSI/ETH_PPS_OUT/I2S3_SD_91") (pintype "bidirectional"))
      (node (ref "U43") (pin "4") (pinfunction "Rx_4") (pintype "passive"))
    )
    (net (code "23") (name "/CAN2_TX") (class "Default")
      (node (ref "U38") (pin "92") (pinfunction "PB6/I2C1_SCL/TIM4_CH1_92") (pintype "bidirectional"))
      (node (ref "U43") (pin "1") (pinfunction "D_1") (pintype "passive"))
    )
    (net (code "24") (name "/CAN_GND") (class "Default")
      (node (ref "P42") (pin "2") (pinfunction "2_2") (pintype "passive"))
      (node (ref "Z1") (pin "3") (pintype "passive"))
      (node (ref "Z2") (pin "3") (pintype "passive"))
    )
    (net (code "25") (name "/DATA") (class "Default")
      (node (ref "P36") (pin "3") (pinfunction "3_3") (pintype "passive"))
      (node (ref "U38") (pin "65") (pinfunction "PC8_65") (pintype "bidirectional"))
    )
    (net (code "26") (name "/DS_I{slash}O") (class "Default")
      (node (ref "U38") (pin "43") (pinfunction "PE12_43") (pintype "bidirectional"))
      (node (ref "U93") (pin "6") (pinfunction "I/O_6") (pintype "bidirectional"))
    )
    (net (code "27") (name "/DS_RST") (class "Default")
      (node (ref "U38") (pin "44") (pinfunction "PE13_44") (pintype "bidirectional"))
      (node (ref "U93") (pin "5") (pinfunction "CE_5") (pintype "input"))
    )
    (net (code "28") (name "/DS_SCLK") (class "Default")
      (node (ref "U38") (pin "42") (pinfunction "PE11_42") (pintype "bidirectional"))
      (node (ref "U93") (pin "7") (pinfunction "SCLK_7") (pintype "input"))
    )
    (net (code "29") (name "/F_CS") (class "Default")
      (node (ref "R153") (pin "1") (pinfunction "1_1") (pintype "passive"))
      (node (ref "U38") (pin "96") (pinfunction "PB9/TIM4_CH4_96") (pintype "bidirectional"))
      (node (ref "U41") (pin "1") (pinfunction "~{CS}_1") (pintype "passive"))
    )
    (net (code "30") (name "/GPRS") (class "Default")
      (node (ref "P37") (pin "3") (pinfunction "3_3") (pintype "passive"))
      (node (ref "U38") (pin "62") (pinfunction "PD15_62") (pintype "bidirectional"))
    )
    (net (code "31") (name "/GPRS_RXD") (class "Default")
      (node (ref "P36") (pin "7") (pinfunction "7_7") (pintype "passive"))
      (node (ref "U38") (pin "78") (pinfunction "PC10/USART4_TX_78") (pintype "bidirectional"))
    )
    (net (code "32") (name "/GPRS_TXD") (class "Default")
      (node (ref "P36") (pin "6") (pinfunction "6_6") (pintype "passive"))
      (node (ref "U38") (pin "79") (pinfunction "PC11/USART4_RX_79") (pintype "bidirectional"))
    )
    (net (code "33") (name "/GPS_PPS") (class "Default")
      (node (ref "P6") (pin "5") (pinfunction "5_5") (pintype "passive"))
      (node (ref "U38") (pin "24") (pinfunction "PA1/USART2_RTS/ADC12_IN1/TIM5_CH2/TIM2_CH2/ETH_MII_RX_CLK/ETH_RMII_REF_CLK_24") (pintype "bidirectional"))
    )
    (net (code "34") (name "/GPS_RX") (class "Default")
      (node (ref "P6") (pin "4") (pinfunction "4_4") (pintype "passive"))
      (node (ref "U38") (pin "25") (pinfunction "PA2/USART2_TX/TIM5_CH3/ADC12_IN2/TIM2_CH3/ETH_MDIO_25") (pintype "bidirectional"))
    )
    (net (code "35") (name "/GPS_TX") (class "Default")
      (node (ref "P6") (pin "3") (pinfunction "3_3") (pintype "passive"))
      (node (ref "U38") (pin "26") (pinfunction "PA3/USART2_RX/TIM5_CH4/ADC12_IN3/TIM2_CH4/ETH_MII_COL_26") (pintype "bidirectional"))
    )
    (net (code "36") (name "/GRESET") (class "Default")
      (node (ref "P37") (pin "6") (pinfunction "6_6") (pintype "passive"))
      (node (ref "U38") (pin "82") (pinfunction "PD1_82") (pintype "bidirectional"))
    )
    (net (code "37") (name "/I2C1_SCL") (class "Default")
      (node (ref "R152") (pin "2") (pinfunction "2_2") (pintype "passive"))
      (node (ref "U38") (pin "47") (pinfunction "PB10/I2C2_SCL/USART3_TX/ETH_MII_RX_ER_47") (pintype "bidirectional"))
      (node (ref "U44") (pin "6") (pinfunction "SCL_6") (pintype "bidirectional"))
    )
    (net (code "38") (name "/I2C1_SDA") (class "Default")
      (node (ref "R154") (pin "2") (pinfunction "2_2") (pintype "passive"))
      (node (ref "U38") (pin "48") (pinfunction "PB11/I2C2_SDA/USART3_RX/ETH_MII_TX_EN/ETH_RMII_TX_EN_48") (pintype "bidirectional"))
      (node (ref "U44") (pin "5") (pinfunction "SDA_5") (pintype "bidirectional"))
    )
    (net (code "39") (name "/IO_OUT") (class "Default")
      (node (ref "P41") (pin "3") (pinfunction "3_3") (pintype "passive"))
      (node (ref "U38") (pin "39") (pinfunction "PE8_39") (pintype "bidirectional"))
    )
    (net (code "40") (name "/LED1") (class "Default")
      (node (ref "LD34") (pin "2") (pinfunction "2_2") (pintype "passive"))
      (node (ref "U38") (pin "85") (pinfunction "PD4_85") (pintype "bidirectional"))
    )
    (net (code "41") (name "/LED2") (class "Default")
      (node (ref "LD35") (pin "2") (pinfunction "2_2") (pintype "passive"))
      (node (ref "U38") (pin "86") (pinfunction "PD5_86") (pintype "bidirectional"))
    )
    (net (code "42") (name "/LED3") (class "Default")
      (node (ref "LD36") (pin "2") (pinfunction "2_2") (pintype "passive"))
      (node (ref "U38") (pin "87") (pinfunction "PD6_87") (pintype "bidirectional"))
    )
    (net (code "43") (name "/LED4") (class "Default")
      (node (ref "LD37") (pin "2") (pinfunction "2_2") (pintype "passive"))
      (node (ref "U38") (pin "88") (pinfunction "PD7_88") (pintype "bidirectional"))
    )
    (net (code "44") (name "/LINKA") (class "Default")
      (node (ref "P36") (pin "1") (pinfunction "1_1") (pintype "passive"))
      (node (ref "U38") (pin "63") (pinfunction "PC6/I2S2_MCK_63") (pintype "bidirectional"))
    )
    (net (code "45") (name "/LINKB") (class "Default")
      (node (ref "P36") (pin "2") (pinfunction "2_2") (pintype "passive"))
      (node (ref "U38") (pin "64") (pinfunction "PC7/I2S3_MCK_64") (pintype "bidirectional"))
    )
    (net (code "46") (name "/OSC32_IN") (class "Default")
      (node (ref "R349") (pin "1") (pinfunction "1_1") (pintype "passive"))
      (node (ref "U38") (pin "8") (pinfunction "PC14-OSC32_IN_8") (pintype "bidirectional"))
    )
    (net (code "47") (name "/OSC32_OUT") (class "Default")
      (node (ref "R350") (pin "1") (pinfunction "1_1") (pintype "passive"))
      (node (ref "U38") (pin "9") (pinfunction "PC15-OSC32_OUT_9") (pintype "bidirectional"))
    )
    (net (code "48") (name "/OSCIN") (class "Default")
      (node (ref "C5") (pin "2") (pinfunction "2_2") (pintype "passive"))
      (node (ref "R138") (pin "2") (pinfunction "2_2") (pintype "passive"))
      (node (ref "U38") (pin "12") (pinfunction "OSC_IN_12") (pintype "input"))
      (node (ref "Y1") (pin "1") (pinfunction "1_1") (pintype "passive"))
    )
    (net (code "49") (name "/OSCOUT") (class "Default")
      (node (ref "C6") (pin "2") (pinfunction "2_2") (pintype "passive"))
      (node (ref "R138") (pin "1") (pinfunction "1_1") (pintype "passive"))
      (node (ref "U38") (pin "13") (pinfunction "OSC_OUT_13") (pintype "output"))
      (node (ref "Y1") (pin "2") (pinfunction "2_2") (pintype "passive"))
    )
    (net (code "50") (name "/PWR_SW") (class "Default")
      (node (ref "P39") (pin "7") (pinfunction "7_7") (pintype "passive"))
      (node (ref "U38") (pin "61") (pinfunction "PD14_61") (pintype "bidirectional"))
    )
    (net (code "51") (name "/RESET") (class "Default")
      (node (ref "C14") (pin "1") (pinfunction "1_1") (pintype "passive"))
      (node (ref "CN1") (pin "15") (pinfunction "nSRST_15") (pintype "passive"))
      (node (ref "R139") (pin "1") (pinfunction "1_1") (pintype "passive"))
      (node (ref "R140") (pin "1") (pinfunction "1_1") (pintype "passive"))
      (node (ref "U38") (pin "14") (pinfunction "NRST_14") (pintype "bidirectional"))
    )
    (net (code "52") (name "/RXD1") (class "Default")
      (node (ref "J3") (pin "2") (pinfunction "2_2") (pintype "passive"))
      (node (ref "U45") (pin "13") (pinfunction "R1IN_13") (pintype "input"))
    )
    (net (code "53") (name "/Relay1") (class "Default")
      (node (ref "P41") (pin "4") (pinfunction "4_4") (pintype "passive"))
      (node (ref "U38") (pin "40") (pinfunction "PE9_40") (pintype "bidirectional"))
    )
    (net (code "54") (name "/Reload") (class "Default")
      (node (ref "P37") (pin "7") (pinfunction "7_7") (pintype "passive"))
      (node (ref "U38") (pin "81") (pinfunction "PD0_81") (pintype "bidirectional"))
    )
    (net (code "55") (name "/SD_CD") (class "Default")
      (node (ref "R150") (pin "2") (pinfunction "2_2") (pintype "passive"))
      (node (ref "U38") (pin "95") (pinfunction "PB8/TIM4_CH3/ETH_MII_TXD3_95") (pintype "bidirectional"))
    )
    (net (code "56") (name "/SD_CS") (class "Default")
      (node (ref "R151") (pin "2") (pinfunction "2_2") (pintype "passive"))
      (node (ref "U38") (pin "93") (pinfunction "PB7/I2C1_SDA/TIM4_CH2_93") (pintype "bidirectional"))
    )
    (net (code "57") (name "/SHUT") (class "Default")
      (node (ref "P36") (pin "10") (pinfunction "10_10") (pintype "passive"))
      (node (ref "U38") (pin "83") (pinfunction "PD2/TIM3_ETR/USART5_RX_83") (pintype "bidirectional"))
    )
    (net (code "58") (name "/SPI1_MISO") (class "Default")
      (node (ref "U38") (pin "31") (pinfunction "PA6/SPI1_MISO/ADC12_IN6/TIM3_CH1_31") (pintype "bidirectional"))
      (node (ref "U41") (pin "2") (pinfunction "DO_2") (pintype "passive"))
    )
    (net (code "59") (name "/SPI1_MOSI") (class "Default")
      (node (ref "U38") (pin "32") (pinfunction "PA7/SPI1_MOSI/ADC12_IN7/TIM3_CH2/ETH_MII_RX_DV/ETH_RMII_CRS_DV_32") (pintype "bidirectional"))
      (node (ref "U41") (pin "5") (pinfunction "DI_5") (pintype "passive"))
    )
    (net (code "60") (name "/SPI1_SCK") (class "Default")
      (node (ref "U38") (pin "30") (pinfunction "PA5/SPI1_SCK/DAC_OUT2/ADC12_IN5_30") (pintype "bidirectional"))
      (node (ref "U41") (pin "6") (pinfunction "CLK_6") (pintype "passive"))
    )
    (net (code "61") (name "/SPI2_MISO") (class "Default")
      (node (ref "J2") (pin "7") (pinfunction "DAT0/DO_7") (pintype "passive"))
      (node (ref "U38") (pin "53") (pinfunction "PB14/SPI2_MISO/TIM1_CH2N/USART3_RTS_53") (pintype "bidirectional"))
    )
    (net (code "62") (name "/SPI2_MOSI") (class "Default")
      (node (ref "J2") (pin "2") (pinfunction "CMD/DI_2") (pintype "passive"))
      (node (ref "U38") (pin "54") (pinfunction "PB15/SPI2_MOSI/I2S2_SD/TIM1_CH3N_54") (pintype "bidirectional"))
    )
    (net (code "63") (name "/SPI2_SCK") (class "Default")
      (node (ref "J2") (pin "5") (pinfunction "CLK/SCLK_5") (pintype "passive"))
      (node (ref "U38") (pin "52") (pinfunction "PB13/SPI2_SCK/I2S2_CK/USART3_CTS/TIM1_CH1N/CAN2_TX/ETH_MII_TXD1/ETH_RMII_TXD1_52") (pintype "bidirectional"))
    )
    (net (code "64") (name "/SW1") (class "Default")
      (node (ref "R361") (pin "1") (pinfunction "1_1") (pintype "passive"))
      (node (ref "S8") (pin "1") (pinfunction "A1_1") (pintype "passive"))
      (node (ref "U38") (pin "1") (pinfunction "PE2/TRACECK_1") (pintype "bidirectional"))
    )
    (net (code "65") (name "/SW2") (class "Default")
      (node (ref "R360") (pin "1") (pinfunction "1_1") (pintype "passive"))
      (node (ref "S8") (pin "2") (pinfunction "A2_2") (pintype "passive"))
      (node (ref "U38") (pin "2") (pinfunction "PE3/TRACED0_2") (pintype "bidirectional"))
    )
    (net (code "66") (name "/SW3") (class "Default")
      (node (ref "R359") (pin "1") (pinfunction "1_1") (pintype "passive"))
      (node (ref "S8") (pin "3") (pinfunction "A3_3") (pintype "passive"))
      (node (ref "U38") (pin "3") (pinfunction "PE4/TRACED1_3") (pintype "bidirectional"))
    )
    (net (code "67") (name "/SW4") (class "Default")
      (node (ref "R358") (pin "1") (pinfunction "1_1") (pintype "passive"))
      (node (ref "S8") (pin "4") (pinfunction "A4_4") (pintype "passive"))
      (node (ref "U38") (pin "4") (pinfunction "PE5/TRACED2_4") (pintype "bidirectional"))
    )
    (net (code "68") (name "/SYSLED") (class "Default")
      (node (ref "J7") (pin "6") (pinfunction "6_6") (pintype "passive"))
      (node (ref "U38") (pin "38") (pinfunction "PE7_38") (pintype "bidirectional"))
    )
    (net (code "69") (name "/TCK{slash}SWCLK") (class "Default")
      (node (ref "CN1") (pin "9") (pinfunction "TCK_9") (pintype "passive"))
      (node (ref "R144") (pin "2") (pinfunction "2_2") (pintype "passive"))
      (node (ref "U38") (pin "76") (pinfunction "PA14/JTCK/SWCLK_76") (pintype "bidirectional"))
    )
    (net (code "70") (name "/TDI") (class "Default")
      (node (ref "CN1") (pin "5") (pinfunction "TDI_5") (pintype "passive"))
      (node (ref "R143") (pin "1") (pinfunction "1_1") (pintype "passive"))
      (node (ref "U38") (pin "77") (pinfunction "PA15/JTDI/SPI3_NSS/I2S3_WS_77") (pintype "bidirectional"))
    )
    (net (code "71") (name "/TDO{slash}SWO") (class "Default")
      (node (ref "CN1") (pin "13") (pinfunction "TDO_13") (pintype "passive"))
      (node (ref "R141") (pin "1") (pinfunction "1_1") (pintype "passive"))
      (node (ref "U38") (pin "89") (pinfunction "PB3/JTDO/SPI3_SCK/I2S3_CK_89") (pintype "bidirectional"))
    )
    (net (code "72") (name "/TMS{slash}SWDIO") (class "Default")
      (node (ref "CN1") (pin "7") (pinfunction "TMS_7") (pintype "passive"))
      (node (ref "R142") (pin "1") (pinfunction "1_1") (pintype "passive"))
      (node (ref "U38") (pin "72") (pinfunction "PA13/JTMS/SWDIO_72") (pintype "bidirectional"))
    )
    (net (code "73") (name "/TRST") (class "Default")
      (node (ref "CN1") (pin "3") (pinfunction "nTRST_3") (pintype "passive"))
      (node (ref "R145") (pin "1") (pinfunction "1_1") (pintype "passive"))
      (node (ref "U38") (pin "90") (pinfunction "PB4/NJTRST/SPI3_MISO_90") (pintype "bidirectional"))
    )
    (net (code "74") (name "/TXD1") (class "Default")
      (node (ref "J3") (pin "3") (pinfunction "3_3") (pintype "passive"))
      (node (ref "U45") (pin "14") (pinfunction "T1OUT_14") (pintype "output"))
    )
    (net (code "75") (name "/USART1_RX") (class "Default")
      (node (ref "U38") (pin "69") (pinfunction "PA10/USART1_RX/TIM1_CH3/OTG_FS_ID_69") (pintype "bidirectional"))
      (node (ref "U45") (pin "12") (pinfunction "R1OUT_12") (pintype "output"))
    )
    (net (code "76") (name "/USART1_TX") (class "Default")
      (node (ref "R149") (pin "1") (pinfunction "1_1") (pintype "passive"))
      (node (ref "U38") (pin "68") (pinfunction "PA9/USART1_TX/TIM1_CH2/OTG_FS_VBUS_68") (pintype "bidirectional"))
      (node (ref "U45") (pin "11") (pinfunction "T1IN_11") (pintype "input"))
    )
    (net (code "77") (name "/VCC+3.8V") (class "Default")
      (node (ref "C37") (pin "1") (pinfunction "1_1") (pintype "passive"))
      (node (ref "D58") (pin "2") (pinfunction "K_2") (pintype "passive"))
      (node (ref "P37") (pin "4") (pinfunction "4_4") (pintype "passive"))
    )
    (net (code "78") (name "/WIFI_RX") (class "Default")
      (node (ref "P38") (pin "3") (pinfunction "3_3") (pintype "passive"))
      (node (ref "U38") (pin "55") (pinfunction "PD8_55") (pintype "bidirectional"))
    )
    (net (code "79") (name "/WIFI_TX") (class "Default")
      (node (ref "P38") (pin "4") (pinfunction "4_4") (pintype "passive"))
      (node (ref "U38") (pin "56") (pinfunction "PD9_56") (pintype "bidirectional"))
    )
    (net (code "80") (name "/WORK") (class "Default")
      (node (ref "P36") (pin "9") (pinfunction "9_9") (pintype "passive"))
      (node (ref "U38") (pin "66") (pinfunction "PC9_66") (pintype "bidirectional"))
    )
    (net (code "81") (name "/WPS") (class "Default")
      (node (ref "P39") (pin "5") (pinfunction "5_5") (pintype "passive"))
      (node (ref "U38") (pin "41") (pinfunction "PE10_41") (pintype "bidirectional"))
    )
    (net (code "82") (name "/_ADC_IN3") (class "Default")
      (node (ref "P30") (pin "2") (pinfunction "2_2") (pintype "passive"))
      (node (ref "R199") (pin "2") (pinfunction "2_2") (pintype "passive"))
    )
    (net (code "83") (name "/_ADC_IN4") (class "Default")
      (node (ref "P11") (pin "1") (pinfunction "1_1") (pintype "passive"))
      (node (ref "R200") (pin "2") (pinfunction "2_2") (pintype "passive"))
    )
    (net (code "84") (name "/_ADC_IN5") (class "Default")
      (node (ref "P10") (pin "1") (pinfunction "1_1") (pintype "passive"))
      (node (ref "R201") (pin "2") (pinfunction "2_2") (pintype "passive"))
    )
    (net (code "85") (name "/_ADC_IN6") (class "Default")
      (node (ref "P12") (pin "1") (pinfunction "1_1") (pintype "passive"))
      (node (ref "R202") (pin "2") (pinfunction "2_2") (pintype "passive"))
    )
    (net (code "86") (name "/_ADC_IN7") (class "Default")
      (node (ref "P9") (pin "1") (pinfunction "1_1") (pintype "passive"))
      (node (ref "R363") (pin "2") (pinfunction "2_2") (pintype "passive"))
    )
    (net (code "87") (name "/nLink") (class "Default")
      (node (ref "P38") (pin "2") (pinfunction "2_2") (pintype "passive"))
      (node (ref "U38") (pin "57") (pinfunction "PD10_57") (pintype "bidirectional"))
    )
    (net (code "88") (name "/nReady") (class "Default")
      (node (ref "P38") (pin "1") (pinfunction "1_1") (pintype "passive"))
      (node (ref "U38") (pin "58") (pinfunction "PD11_58") (pintype "bidirectional"))
    )
    (net (code "89") (name "/nReload") (class "Default")
      (node (ref "P39") (pin "2") (pinfunction "2_2") (pintype "passive"))
      (node (ref "U38") (pin "59") (pinfunction "PD12_59") (pintype "bidirectional"))
    )
    (net (code "90") (name "/nReset") (class "Default")
      (node (ref "P39") (pin "1") (pinfunction "1_1") (pintype "passive"))
      (node (ref "U38") (pin "60") (pinfunction "PD13_60") (pintype "bidirectional"))
    )
    (net (code "91") (name "GND") (class "Default")
      (node (ref "BT1") (pin "2") (pinfunction "-_2") (pintype "passive"))
      (node (ref "C14") (pin "2") (pinfunction "2_2") (pintype "passive"))
      (node (ref "C15") (pin "1") (pinfunction "1_1") (pintype "passive"))
      (node (ref "C16") (pin "1") (pinfunction "1_1") (pintype "passive"))
      (node (ref "C17") (pin "1") (pinfunction "1_1") (pintype "passive"))
      (node (ref "C18") (pin "1") (pinfunction "1_1") (pintype "passive"))
      (node (ref "C19") (pin "1") (pinfunction "1_1") (pintype "passive"))
      (node (ref "C20") (pin "1") (pinfunction "1_1") (pintype "passive"))
      (node (ref "C21") (pin "1") (pinfunction "1_1") (pintype "passive"))
      (node (ref "C22") (pin "1") (pinfunction "1_1") (pintype "passive"))
      (node (ref "C29") (pin "1") (pinfunction "1_1") (pintype "passive"))
      (node (ref "C31") (pin "1") (pinfunction "1_1") (pintype "passive"))
      (node (ref "C32") (pin "1") (pinfunction "1_1") (pintype "passive"))
      (node (ref "C33") (pin "1") (pinfunction "1_1") (pintype "passive"))
      (node (ref "C34") (pin "1") (pinfunction "1_1") (pintype "passive"))
      (node (ref "C36") (pin "1") (pinfunction "1_1") (pintype "passive"))
      (node (ref "C37") (pin "2") (pinfunction "2_2") (pintype "passive"))
      (node (ref "C44") (pin "1") (pinfunction "1_1") (pintype "passive"))
      (node (ref "C47") (pin "1") (pinfunction "1_1") (pintype "passive"))
      (node (ref "C49") (pin "2") (pinfunction "2_2") (pintype "passive"))
      (node (ref "C5") (pin "1") (pinfunction "1_1") (pintype "passive"))
      (node (ref "C51") (pin "2") (pinfunction "2_2") (pintype "passive"))
      (node (ref "C53") (pin "2") (pinfunction "2_2") (pintype "passive"))
      (node (ref "C55") (pin "2") (pinfunction "2_2") (pintype "passive"))
      (node (ref "C56") (pin "2") (pinfunction "2_2") (pintype "passive"))
      (node (ref "C57") (pin "2") (pinfunction "2_2") (pintype "passive"))
      (node (ref "C6") (pin "1") (pinfunction "1_1") (pintype "passive"))
      (node (ref "C69") (pin "1") (pinfunction "1_1") (pintype "passive"))
      (node (ref "C70") (pin "1") (pinfunction "1_1") (pintype "passive"))
      (node (ref "C72") (pin "2") (pinfunction "2_2") (pintype "passive"))
      (node (ref "C73") (pin "1") (pinfunction "1_1") (pintype "passive"))
      (node (ref "C74") (pin "2") (pinfunction "2_2") (pintype "passive"))
      (node (ref "C75") (pin "1") (pinfunction "1_1") (pintype "passive"))
      (node (ref "C76") (pin "2") (pinfunction "2_2") (pintype "passive"))
      (node (ref "C79") (pin "1") (pintype "passive"))
      (node (ref "C80") (pin "2") (pintype "passive"))
      (node (ref "C81") (pin "1") (pintype "passive"))
      (node (ref "CN1") (pin "10") (pinfunction "GND4_10") (pintype "passive"))
      (node (ref "CN1") (pin "12") (pinfunction "GND5_12") (pintype "passive"))
      (node (ref "CN1") (pin "14") (pinfunction "GND6_14") (pintype "passive"))
      (node (ref "CN1") (pin "16") (pinfunction "GND7_16") (pintype "passive"))
      (node (ref "CN1") (pin "18") (pinfunction "GND8_18") (pintype "passive"))
      (node (ref "CN1") (pin "20") (pinfunction "GND9_20") (pintype "passive"))
      (node (ref "CN1") (pin "4") (pinfunction "GND1_4") (pintype "passive"))
      (node (ref "CN1") (pin "6") (pinfunction "GND2_6") (pintype "passive"))
      (node (ref "CN1") (pin "8") (pinfunction "GND3_8") (pintype "passive"))
      (node (ref "D60") (pin "1") (pinfunction "A_1") (pintype "passive"))
      (node (ref "J2") (pin "12") (pinfunction "GND_12") (pintype "passive"))
      (node (ref "J2") (pin "13") (pinfunction "GND_13") (pintype "passive"))
      (node (ref "J2") (pin "3") (pinfunction "VSS1_3") (pintype "passive"))
      (node (ref "J2") (pin "6") (pinfunction "VSS2_6") (pintype "passive"))
      (node (ref "J3") (pin "5") (pinfunction "5_5") (pintype "passive"))
      (node (ref "J7") (pin "4") (pinfunction "4_4") (pintype "passive"))
      (node (ref "J7") (pin "5") (pinfunction "5_5") (pintype "passive"))
      (node (ref "KEY2") (pin "1") (pinfunction "1_1") (pintype "passive"))
      (node (ref "L2") (pin "1") (pinfunction "1_1") (pintype "passive"))
      (node (ref "LD83") (pin "2") (pinfunction "2_2") (pintype "passive"))
      (node (ref "P10") (pin "2") (pinfunction "2_2") (pintype "passive"))
      (node (ref "P11") (pin "2") (pinfunction "2_2") (pintype "passive"))
      (node (ref "P12") (pin "2") (pinfunction "2_2") (pintype "passive"))
      (node (ref "P30") (pin "3") (pinfunction "3_3") (pintype "passive"))
      (node (ref "P36") (pin "11") (pinfunction "11_11") (pintype "passive"))
      (node (ref "P36") (pin "12") (pinfunction "12_12") (pintype "passive"))
      (node (ref "P38") (pin "5") (pinfunction "5_5") (pintype "passive"))
      (node (ref "P38") (pin "6") (pinfunction "6_6") (pintype "passive"))
      (node (ref "P4") (pin "4") (pinfunction "4_4") (pintype "passive"))
      (node (ref "P4") (pin "5") (pinfunction "5_5") (pintype "passive"))
      (node (ref "P41") (pin "2") (pinfunction "2_2") (pintype "passive"))
      (node (ref "P42") (pin "1") (pinfunction "1_1") (pintype "passive"))
      (node (ref "P6") (pin "2") (pinfunction "2_2") (pintype "passive"))
      (node (ref "P7") (pin "1") (pinfunction "1_1") (pintype "passive"))
      (node (ref "P8") (pin "1") (pinfunction "1_1") (pintype "passive"))
      (node (ref "P9") (pin "2") (pinfunction "2_2") (pintype "passive"))
      (node (ref "Q9") (pin "E") (pintype "passive"))
      (node (ref "R137") (pin "2") (pinfunction "2_2") (pintype "passive"))
      (node (ref "R144") (pin "1") (pinfunction "1_1") (pintype "passive"))
      (node (ref "R146") (pin "1") (pinfunction "1_1") (pintype "passive"))
      (node (ref "R147") (pin "1") (pinfunction "1_1") (pintype "passive"))
      (node (ref "R157") (pin "2") (pinfunction "2_2") (pintype "passive"))
      (node (ref "R158") (pin "2") (pinfunction "2_2") (pintype "passive"))
      (node (ref "R172") (pin "1") (pinfunction "1_1") (pintype "passive"))
      (node (ref "R177") (pin "1") (pinfunction "1_1") (pintype "passive"))
      (node (ref "R184") (pin "2") (pinfunction "2_2") (pintype "passive"))
      (node (ref "R191") (pin "2") (pinfunction "2_2") (pintype "passive"))
      (node (ref "R362") (pin "1") (pinfunction "1_1") (pintype "passive"))
      (node (ref "S8") (pin "5") (pinfunction "B4_5") (pintype "passive"))
      (node (ref "S8") (pin "6") (pinfunction "B3_6") (pintype "passive"))
      (node (ref "S8") (pin "7") (pinfunction "B2_7") (pintype "passive"))
      (node (ref "S8") (pin "8") (pinfunction "B1_8") (pintype "passive"))
      (node (ref "U38") (pin "10") (pinfunction "VSS_5_10") (pintype "passive"))
      (node (ref "U38") (pin "27") (pinfunction "VSS_4_27") (pintype "passive"))
      (node (ref "U38") (pin "49") (pinfunction "VSS_1_49") (pintype "passive"))
      (node (ref "U38") (pin "74") (pinfunction "VSS_2_74") (pintype "passive"))
      (node (ref "U38") (pin "99") (pinfunction "VSS_3_99") (pintype "passive"))
      (node (ref "U41") (pin "4") (pinfunction "GND_4") (pintype "passive"))
      (node (ref "U42") (pin "2") (pinfunction "GND_2") (pintype "passive"))
      (node (ref "U43") (pin "2") (pinfunction "GND_2") (pintype "passive"))
      (node (ref "U44") (pin "1") (pinfunction "A0_1") (pintype "input"))
      (node (ref "U44") (pin "2") (pinfunction "A1_2") (pintype "input"))
      (node (ref "U44") (pin "3") (pinfunction "NC_3") (pintype "passive"))
      (node (ref "U44") (pin "4") (pinfunction "GND_4") (pintype "power_in"))
      (node (ref "U44") (pin "7") (pinfunction "WP_7") (pintype "input"))
      (node (ref "U45") (pin "15") (pinfunction "GND_15") (pintype "power_in"))
      (node (ref "U49") (pin "4") (pinfunction "GND_4") (pintype "passive"))
      (node (ref "U50") (pin "4") (pinfunction "GND_4") (pintype "passive"))
      (node (ref "U92") (pin "1") (pinfunction "GND_1") (pintype "passive"))
      (node (ref "U93") (pin "4") (pinfunction "GND_4") (pintype "power_in"))
      (node (ref "Z5") (pin "3") (pintype "passive"))
    )
    (net (code "92") (name "Net-(BT1-+)") (class "Default")
      (node (ref "BT1") (pin "1") (pinfunction "+_1") (pintype "passive"))
      (node (ref "U93") (pin "8") (pinfunction "Vcc1_8") (pintype "power_in"))
    )
    (net (code "93") (name "Net-(BZ2-B)") (class "Default")
      (node (ref "BZ2") (pin "2") (pinfunction "B_2") (pintype "passive"))
      (node (ref "R167") (pin "1") (pinfunction "1_1") (pintype "passive"))
    )
    (net (code "94") (name "Net-(C47-Pad2)") (class "Default")
      (node (ref "C47") (pin "2") (pinfunction "2_2") (pintype "passive"))
      (node (ref "R173") (pin "1") (pinfunction "1_1") (pintype "passive"))
      (node (ref "U50") (pin "5") (pintype "passive"))
    )
    (net (code "95") (name "Net-(C69-Pad2)") (class "Default")
      (node (ref "C69") (pin "2") (pinfunction "2_2") (pintype "passive"))
      (node (ref "R349") (pin "2") (pinfunction "2_2") (pintype "passive"))
      (node (ref "Y2") (pin "1") (pinfunction "1_1") (pintype "passive"))
    )
    (net (code "96") (name "Net-(C70-Pad2)") (class "Default")
      (node (ref "C70") (pin "2") (pinfunction "2_2") (pintype "passive"))
      (node (ref "R350") (pin "2") (pinfunction "2_2") (pintype "passive"))
      (node (ref "Y2") (pin "2") (pinfunction "2_2") (pintype "passive"))
    )
    (net (code "97") (name "Net-(CN1-DBGACK)") (class "Default")
      (node (ref "CN1") (pin "19") (pinfunction "DBGACK_19") (pintype "passive"))
      (node (ref "R370") (pin "2") (pinfunction "2_2") (pintype "passive"))
    )
    (net (code "98") (name "Net-(CN1-RTCK)") (class "Default")
      (node (ref "CN1") (pin "11") (pinfunction "RTCK_11") (pintype "passive"))
      (node (ref "R146") (pin "2") (pinfunction "2_2") (pintype "passive"))
    )
    (net (code "99") (name "Net-(DZ1-V-)") (class "Default")
      (node (ref "DZ1") (pin "1") (pinfunction "V-_1") (pintype "power_in"))
      (node (ref "R191") (pin "1") (pinfunction "1_1") (pintype "passive"))
      (node (ref "U49") (pin "5") (pintype "passive"))
    )
    (net (code "100") (name "Net-(J2-CD)") (class "Default")
      (node (ref "J2") (pin "10") (pinfunction "CD_10") (pintype "passive"))
      (node (ref "R150") (pin "1") (pinfunction "1_1") (pintype "passive"))
      (node (ref "R155") (pin "2") (pinfunction "2_2") (pintype "passive"))
    )
    (net (code "101") (name "Net-(J2-CD{slash}DAT3{slash}CS)") (class "Default")
      (node (ref "J2") (pin "1") (pinfunction "CD/DAT3/CS_1") (pintype "passive"))
      (node (ref "R151") (pin "1") (pinfunction "1_1") (pintype "passive"))
      (node (ref "R156") (pin "1") (pinfunction "1_1") (pintype "passive"))
    )
    (net (code "102") (name "Net-(KEY2-Pad2)") (class "Default")
      (node (ref "KEY2") (pin "2") (pinfunction "2_2") (pintype "passive"))
      (node (ref "R139") (pin "2") (pinfunction "2_2") (pintype "passive"))
    )
    (net (code "103") (name "Net-(LD34-Pad1)") (class "Default")
      (node (ref "LD34") (pin "1") (pinfunction "1_1") (pintype "passive"))
      (node (ref "R161") (pin "2") (pinfunction "2_2") (pintype "passive"))
    )
    (net (code "104") (name "Net-(LD35-Pad1)") (class "Default")
      (node (ref "LD35") (pin "1") (pinfunction "1_1") (pintype "passive"))
      (node (ref "R162") (pin "2") (pinfunction "2_2") (pintype "passive"))
    )
    (net (code "105") (name "Net-(LD36-Pad1)") (class "Default")
      (node (ref "LD36") (pin "1") (pinfunction "1_1") (pintype "passive"))
      (node (ref "R163") (pin "2") (pinfunction "2_2") (pintype "passive"))
    )
    (net (code "106") (name "Net-(LD37-Pad1)") (class "Default")
      (node (ref "LD37") (pin "1") (pinfunction "1_1") (pintype "passive"))
      (node (ref "R164") (pin "2") (pinfunction "2_2") (pintype "passive"))
    )
    (net (code "107") (name "Net-(LD83-Pad1)") (class "Default")
      (node (ref "LD83") (pin "1") (pinfunction "1_1") (pintype "passive"))
      (node (ref "R369") (pin "2") (pinfunction "2_2") (pintype "passive"))
    )
    (net (code "108") (name "Net-(P8-Pad2)") (class "Default")
      (node (ref "P8") (pin "2") (pinfunction "2_2") (pintype "passive"))
      (node (ref "R174") (pin "2") (pinfunction "2_2") (pintype "passive"))
      (node (ref "R362") (pin "2") (pinfunction "2_2") (pintype "passive"))
    )
    (net (code "109") (name "Net-(Q9-PadB)") (class "Default")
      (node (ref "Q9") (pin "B") (pintype "passive"))
      (node (ref "R165") (pin "1") (pinfunction "1_1") (pintype "passive"))
    )
    (net (code "110") (name "Net-(Q9-PadC)") (class "Default")
      (node (ref "Q9") (pin "C") (pintype "passive"))
      (node (ref "R167") (pin "2") (pinfunction "2_2") (pintype "passive"))
    )
    (net (code "111") (name "Net-(Q10-B)") (class "Default")
      (node (ref "Q10") (pin "1") (pinfunction "B_1") (pintype "passive"))
      (node (ref "Q11") (pin "2") (pinfunction "E_2") (pintype "passive"))
    )
    (net (code "112") (name "Net-(Q10-C)") (class "Default")
      (node (ref "P8") (pin "3") (pinfunction "3_3") (pintype "passive"))
      (node (ref "Q10") (pin "3") (pinfunction "C_3") (pintype "passive"))
      (node (ref "Q11") (pin "3") (pinfunction "C_3") (pintype "passive"))
      (node (ref "R175") (pin "2") (pinfunction "2_2") (pintype "passive"))
    )
    (net (code "113") (name "Net-(Q10-E)") (class "Default")
      (node (ref "Q10") (pin "2") (pinfunction "E_2") (pintype "passive"))
      (node (ref "R171") (pin "1") (pinfunction "1_1") (pintype "passive"))
      (node (ref "U49") (pin "6") (pintype "passive"))
    )
    (net (code "114") (name "Net-(Q11-B)") (class "Default")
      (node (ref "Q11") (pin "1") (pinfunction "B_1") (pintype "passive"))
      (node (ref "R176") (pin "2") (pinfunction "2_2") (pintype "passive"))
    )
    (net (code "115") (name "Net-(R174-Pad1)") (class "Default")
      (node (ref "R174") (pin "1") (pinfunction "1_1") (pintype "passive"))
      (node (ref "R179") (pin "1") (pinfunction "1_1") (pintype "passive"))
      (node (ref "U49") (pin "2") (pintype "passive"))
    )
    (net (code "116") (name "Net-(R175-Pad1)") (class "Default")
      (node (ref "R175") (pin "1") (pinfunction "1_1") (pintype "passive"))
      (node (ref "R177") (pin "2") (pinfunction "2_2") (pintype "passive"))
      (node (ref "U49") (pin "3") (pintype "passive"))
    )
    (net (code "117") (name "Net-(R176-Pad1)") (class "Default")
      (node (ref "R176") (pin "1") (pinfunction "1_1") (pintype "passive"))
      (node (ref "U49") (pin "7") (pintype "passive"))
    )
    (net (code "118") (name "Net-(R179-Pad2)") (class "Default")
      (node (ref "R179") (pin "2") (pinfunction "2_2") (pintype "passive"))
      (node (ref "R183") (pin "2") (pinfunction "2_2") (pintype "passive"))
      (node (ref "R184") (pin "1") (pinfunction "1_1") (pintype "passive"))
    )
    (net (code "119") (name "Net-(R183-Pad1)") (class "Default")
      (node (ref "R183") (pin "1") (pinfunction "1_1") (pintype "passive"))
      (node (ref "R185") (pin "1") (pinfunction "1_1") (pintype "passive"))
      (node (ref "U49") (pin "1") (pintype "passive"))
    )
    (net (code "120") (name "Net-(R190-Pad1)") (class "Default")
      (node (ref "R190") (pin "1") (pinfunction "1_1") (pintype "passive"))
      (node (ref "U50") (pin "6") (pintype "passive"))
      (node (ref "U50") (pin "7") (pintype "passive"))
    )
    (net (code "121") (name "Net-(U38-PB2{slash}BOOT1)") (class "Default")
      (node (ref "R137") (pin "1") (pinfunction "1_1") (pintype "passive"))
      (node (ref "U38") (pin "37") (pinfunction "PB2/BOOT1_37") (pintype "bidirectional"))
    )
    (net (code "122") (name "Net-(U42-CANH)") (class "Default")
      (node (ref "R354") (pin "1") (pinfunction "1_1") (pintype "passive"))
      (node (ref "U42") (pin "7") (pinfunction "CANH_7") (pintype "passive"))
    )
    (net (code "123") (name "Net-(U42-CANL)") (class "Default")
      (node (ref "R355") (pin "1") (pinfunction "1_1") (pintype "passive"))
      (node (ref "U42") (pin "6") (pinfunction "CANL_6") (pintype "passive"))
    )
    (net (code "124") (name "Net-(U42-Rs)") (class "Default")
      (node (ref "R157") (pin "1") (pinfunction "1_1") (pintype "passive"))
      (node (ref "U42") (pin "8") (pinfunction "Rs_8") (pintype "passive"))
    )
    (net (code "125") (name "Net-(U43-CANH)") (class "Default")
      (node (ref "R356") (pin "1") (pinfunction "1_1") (pintype "passive"))
      (node (ref "U43") (pin "7") (pinfunction "CANH_7") (pintype "passive"))
    )
    (net (code "126") (name "Net-(U43-CANL)") (class "Default")
      (node (ref "R357") (pin "1") (pinfunction "1_1") (pintype "passive"))
      (node (ref "U43") (pin "6") (pinfunction "CANL_6") (pintype "passive"))
    )
    (net (code "127") (name "Net-(U43-Rs)") (class "Default")
      (node (ref "R158") (pin "1") (pinfunction "1_1") (pintype "passive"))
      (node (ref "U43") (pin "8") (pinfunction "Rs_8") (pintype "passive"))
    )
    (net (code "128") (name "Net-(U45-C1+)") (class "Default")
      (node (ref "C30") (pin "2") (pinfunction "2_2") (pintype "passive"))
      (node (ref "U45") (pin "1") (pinfunction "C1+_1") (pintype "passive"))
    )
    (net (code "129") (name "Net-(U45-C1-)") (class "Default")
      (node (ref "C30") (pin "1") (pinfunction "1_1") (pintype "passive"))
      (node (ref "U45") (pin "3") (pinfunction "C1-_3") (pintype "passive"))
    )
    (net (code "130") (name "Net-(U45-C2+)") (class "Default")
      (node (ref "C28") (pin "2") (pinfunction "2_2") (pintype "passive"))
      (node (ref "U45") (pin "4") (pinfunction "C2+_4") (pintype "passive"))
    )
    (net (code "131") (name "Net-(U45-C2-)") (class "Default")
      (node (ref "C28") (pin "1") (pinfunction "1_1") (pintype "passive"))
      (node (ref "U45") (pin "5") (pinfunction "C2-_5") (pintype "passive"))
    )
    (net (code "132") (name "Net-(U45-VDD)") (class "Default")
      (node (ref "C35") (pin "1") (pinfunction "1_1") (pintype "passive"))
      (node (ref "U45") (pin "2") (pinfunction "VDD_2") (pintype "power_in"))
    )
    (net (code "133") (name "Net-(U45-VEE)") (class "Default")
      (node (ref "C34") (pin "2") (pinfunction "2_2") (pintype "passive"))
      (node (ref "U45") (pin "6") (pinfunction "VEE_6") (pintype "power_in"))
    )
    (net (code "134") (name "Net-(U93-X1)") (class "Default")
      (node (ref "U93") (pin "2") (pinfunction "X1_2") (pintype "input"))
      (node (ref "Y3") (pin "2") (pintype "passive"))
    )
    (net (code "135") (name "Net-(U93-X2)") (class "Default")
      (node (ref "U93") (pin "3") (pinfunction "X2_3") (pintype "input"))
      (node (ref "Y3") (pin "1") (pintype "passive"))
    )
    (net (code "136") (name "VDDA") (class "Default")
      (node (ref "C7") (pin "2") (pinfunction "2_2") (pintype "passive"))
      (node (ref "C8") (pin "2") (pinfunction "2_2") (pintype "passive"))
      (node (ref "L1") (pin "2") (pinfunction "2_2") (pintype "passive"))
      (node (ref "L3") (pin "1") (pinfunction "1_1") (pintype "passive"))
      (node (ref "U38") (pin "22") (pinfunction "VDDA_22") (pintype "passive"))
    )
    (net (code "137") (name "VREF+") (class "Default")
      (node (ref "C11") (pin "2") (pinfunction "2_2") (pintype "passive"))
      (node (ref "C13") (pin "1") (pinfunction "1_1") (pintype "passive"))
      (node (ref "C9") (pin "2") (pinfunction "2_2") (pintype "passive"))
      (node (ref "L3") (pin "2") (pinfunction "2_2") (pintype "passive"))
      (node (ref "U38") (pin "21") (pinfunction "VREF+_21") (pintype "passive"))
    )
    (net (code "138") (name "VREF-") (class "Default")
      (node (ref "C11") (pin "1") (pinfunction "1_1") (pintype "passive"))
      (node (ref "C13") (pin "2") (pinfunction "2_2") (pintype "passive"))
      (node (ref "C9") (pin "1") (pinfunction "1_1") (pintype "passive"))
      (node (ref "L4") (pin "2") (pinfunction "2_2") (pintype "passive"))
      (node (ref "U38") (pin "20") (pinfunction "VREF-_20") (pintype "passive"))
    )
    (net (code "139") (name "VS+") (class "Default")
      (node (ref "J1") (pin "1") (pinfunction "1_1") (pintype "passive"))
      (node (ref "J8") (pin "1") (pinfunction "1_1") (pintype "passive"))
      (node (ref "J8") (pin "2") (pinfunction "2_2") (pintype "passive"))
      (node (ref "P40") (pin "1") (pinfunction "1_1") (pintype "passive"))
      (node (ref "P40") (pin "2") (pinfunction "2_2") (pintype "passive"))
    )
    (net (code "140") (name "VS-") (class "Default")
      (node (ref "J1") (pin "2") (pinfunction "2_2") (pintype "passive"))
      (node (ref "J8") (pin "5") (pinfunction "5_5") (pintype "passive"))
      (node (ref "J8") (pin "6") (pinfunction "6_6") (pintype "passive"))
      (node (ref "P40") (pin "5") (pinfunction "5_5") (pintype "passive"))
      (node (ref "P40") (pin "6") (pinfunction "6_6") (pintype "passive"))
      (node (ref "P42") (pin "3") (pinfunction "3_3") (pintype "passive"))
    )
    (net (code "141") (name "VSSA") (class "Default")
      (node (ref "C7") (pin "1") (pinfunction "1_1") (pintype "passive"))
      (node (ref "C8") (pin "1") (pinfunction "1_1") (pintype "passive"))
      (node (ref "L2") (pin "2") (pinfunction "2_2") (pintype "passive"))
      (node (ref "L4") (pin "1") (pinfunction "1_1") (pintype "passive"))
      (node (ref "U38") (pin "19") (pinfunction "VSSA_19") (pintype "passive"))
    )
    (net (code "142") (name "unconnected-(CN1-DBGRQ-Pad17)") (class "Default")
      (node (ref "CN1") (pin "17") (pinfunction "DBGRQ_17") (pintype "passive"))
    )
    (net (code "143") (name "unconnected-(DZ1-NC-Pad3)") (class "Default")
      (node (ref "DZ1") (pin "3") (pinfunction "NC_3") (pintype "passive"))
    )
    (net (code "144") (name "unconnected-(J2-DAT1-Pad8)") (class "Default")
      (node (ref "J2") (pin "8") (pinfunction "DAT1_8") (pintype "passive"))
    )
    (net (code "145") (name "unconnected-(J2-DAT2-Pad9)") (class "Default")
      (node (ref "J2") (pin "9") (pinfunction "DAT2_9") (pintype "passive"))
    )
    (net (code "146") (name "unconnected-(J2-WP-Pad11)") (class "Default")
      (node (ref "J2") (pin "11") (pinfunction "WP_11") (pintype "passive"))
    )
    (net (code "147") (name "unconnected-(J3-MH1-Pad10)") (class "Default")
      (node (ref "J3") (pin "10") (pinfunction "MH1_10") (pintype "passive"))
    )
    (net (code "148") (name "unconnected-(J3-MH2-Pad11)") (class "Default")
      (node (ref "J3") (pin "11") (pinfunction "MH2_11") (pintype "passive"))
    )
    (net (code "149") (name "unconnected-(J3-Pad1)") (class "Default")
      (node (ref "J3") (pin "1") (pinfunction "1_1") (pintype "passive"))
    )
    (net (code "150") (name "unconnected-(J3-Pad4)") (class "Default")
      (node (ref "J3") (pin "4") (pinfunction "4_4") (pintype "passive"))
    )
    (net (code "151") (name "unconnected-(J3-Pad6)") (class "Default")
      (node (ref "J3") (pin "6") (pinfunction "6_6") (pintype "passive"))
    )
    (net (code "152") (name "unconnected-(J3-Pad7)") (class "Default")
      (node (ref "J3") (pin "7") (pinfunction "7_7") (pintype "passive"))
    )
    (net (code "153") (name "unconnected-(J3-Pad8)") (class "Default")
      (node (ref "J3") (pin "8") (pinfunction "8_8") (pintype "passive"))
    )
    (net (code "154") (name "unconnected-(J3-Pad9)") (class "Default")
      (node (ref "J3") (pin "9") (pinfunction "9_9") (pintype "passive"))
    )
    (net (code "155") (name "unconnected-(J7-Pad3)") (class "Default")
      (node (ref "J7") (pin "3") (pinfunction "3_3") (pintype "passive"))
    )
    (net (code "156") (name "unconnected-(J8-Pad3)") (class "Default")
      (node (ref "J8") (pin "3") (pinfunction "3_3") (pintype "passive"))
    )
    (net (code "157") (name "unconnected-(J8-Pad4)") (class "Default")
      (node (ref "J8") (pin "4") (pinfunction "4_4") (pintype "passive"))
    )
    (net (code "158") (name "unconnected-(P36-Pad4)") (class "Default")
      (node (ref "P36") (pin "4") (pinfunction "4_4") (pintype "passive"))
    )
    (net (code "159") (name "unconnected-(P36-Pad5)") (class "Default")
      (node (ref "P36") (pin "5") (pinfunction "5_5") (pintype "passive"))
    )
    (net (code "160") (name "unconnected-(P36-Pad8)") (class "Default")
      (node (ref "P36") (pin "8") (pinfunction "8_8") (pintype "passive"))
    )
    (net (code "161") (name "unconnected-(P37-Pad5)") (class "Default")
      (node (ref "P37") (pin "5") (pinfunction "5_5") (pintype "passive"))
    )
    (net (code "162") (name "unconnected-(P37-Pad8)") (class "Default")
      (node (ref "P37") (pin "8") (pinfunction "8_8") (pintype "passive"))
    )
    (net (code "163") (name "unconnected-(P37-Pad9)") (class "Default")
      (node (ref "P37") (pin "9") (pinfunction "9_9") (pintype "passive"))
    )
    (net (code "164") (name "unconnected-(P37-Pad10)") (class "Default")
      (node (ref "P37") (pin "10") (pinfunction "10_10") (pintype "passive"))
    )
    (net (code "165") (name "unconnected-(P37-Pad11)") (class "Default")
      (node (ref "P37") (pin "11") (pinfunction "11_11") (pintype "passive"))
    )
    (net (code "166") (name "unconnected-(P39-Pad3)") (class "Default")
      (node (ref "P39") (pin "3") (pinfunction "3_3") (pintype "passive"))
    )
    (net (code "167") (name "unconnected-(P39-Pad4)") (class "Default")
      (node (ref "P39") (pin "4") (pinfunction "4_4") (pintype "passive"))
    )
    (net (code "168") (name "unconnected-(P39-Pad6)") (class "Default")
      (node (ref "P39") (pin "6") (pinfunction "6_6") (pintype "passive"))
    )
    (net (code "169") (name "unconnected-(P40-Pad3)") (class "Default")
      (node (ref "P40") (pin "3") (pinfunction "3_3") (pintype "passive"))
    )
    (net (code "170") (name "unconnected-(P40-Pad4)") (class "Default")
      (node (ref "P40") (pin "4") (pinfunction "4_4") (pintype "passive"))
    )
    (net (code "171") (name "unconnected-(U38-NC-Pad73)") (class "Default")
      (node (ref "U38") (pin "73") (pinfunction "NC_73") (pintype "passive"))
    )
    (net (code "172") (name "unconnected-(U38-PA8{slash}USART1_CK{slash}OTG_FS_SOF{slash}TIM1_CH1{slash}MCO-Pad67)") (class "Default")
      (node (ref "U38") (pin "67") (pinfunction "PA8/USART1_CK/OTG_FS_SOF/TIM1_CH1/MCO_67") (pintype "bidirectional"))
    )
    (net (code "173") (name "unconnected-(U38-PB12{slash}SPI2_NSS{slash}I2S2_WS{slash}I2C2_SMBA{slash}USART3_CK{slash}TIM1_BKIN{slash}CAN2_RX{slash}ETH_MII_TXD0{slash}ETH_RMII_TXD0-Pad51)") (class "Default")
      (node (ref "U38") (pin "51") (pinfunction "PB12/SPI2_NSS/I2S2_WS/I2C2_SMBA/USART3_CK/TIM1_BKIN/CAN2_RX/ETH_MII_TXD0/ETH_RMII_TXD0_51") (pintype "bidirectional"))
    )
    (net (code "174") (name "unconnected-(U38-PC12{slash}USART5_TX-Pad80)") (class "Default")
      (node (ref "U38") (pin "80") (pinfunction "PC12/USART5_TX_80") (pintype "bidirectional"))
    )
    (net (code "175") (name "unconnected-(U38-PC13-TAMPER-RTC-Pad7)") (class "Default")
      (node (ref "U38") (pin "7") (pinfunction "PC13-TAMPER-RTC_7") (pintype "bidirectional"))
    )
    (net (code "176") (name "unconnected-(U38-PE0{slash}TIM4_ETR-Pad97)") (class "Default")
      (node (ref "U38") (pin "97") (pinfunction "PE0/TIM4_ETR_97") (pintype "bidirectional"))
    )
    (net (code "177") (name "unconnected-(U38-PE1-Pad98)") (class "Default")
      (node (ref "U38") (pin "98") (pinfunction "PE1_98") (pintype "bidirectional"))
    )
    (net (code "178") (name "unconnected-(U38-PE6{slash}TRACED3-Pad5)") (class "Default")
      (node (ref "U38") (pin "5") (pinfunction "PE6/TRACED3_5") (pintype "bidirectional"))
    )
    (net (code "179") (name "unconnected-(U38-PE14-Pad45)") (class "Default")
      (node (ref "U38") (pin "45") (pinfunction "PE14_45") (pintype "bidirectional"))
    )
    (net (code "180") (name "unconnected-(U38-PE15-Pad46)") (class "Default")
      (node (ref "U38") (pin "46") (pinfunction "PE15_46") (pintype "bidirectional"))
    )
    (net (code "181") (name "unconnected-(U38-VBAT-Pad6)") (class "Default")
      (node (ref "U38") (pin "6") (pinfunction "VBAT_6") (pintype "power_in"))
    )
    (net (code "182") (name "unconnected-(U42-Vref-Pad5)") (class "Default")
      (node (ref "U42") (pin "5") (pinfunction "Vref_5") (pintype "passive"))
    )
    (net (code "183") (name "unconnected-(U43-Vref-Pad5)") (class "Default")
      (node (ref "U43") (pin "5") (pinfunction "Vref_5") (pintype "passive"))
    )
    (net (code "184") (name "unconnected-(U45-R2IN-Pad8)") (class "Default")
      (node (ref "U45") (pin "8") (pinfunction "R2IN_8") (pintype "input"))
    )
    (net (code "185") (name "unconnected-(U45-R2OUT-Pad9)") (class "Default")
      (node (ref "U45") (pin "9") (pinfunction "R2OUT_9") (pintype "output"))
    )
    (net (code "186") (name "unconnected-(U45-T2IN-Pad10)") (class "Default")
      (node (ref "U45") (pin "10") (pinfunction "T2IN_10") (pintype "input"))
    )
    (net (code "187") (name "unconnected-(U45-T2OUT-Pad7)") (class "Default")
      (node (ref "U45") (pin "7") (pinfunction "T2OUT_7") (pintype "output"))
    )
  )
)
